# HDMI_RGB_LVDS_fertig_V6.net
KiCad netlist of a schematic drawn in EAGLE
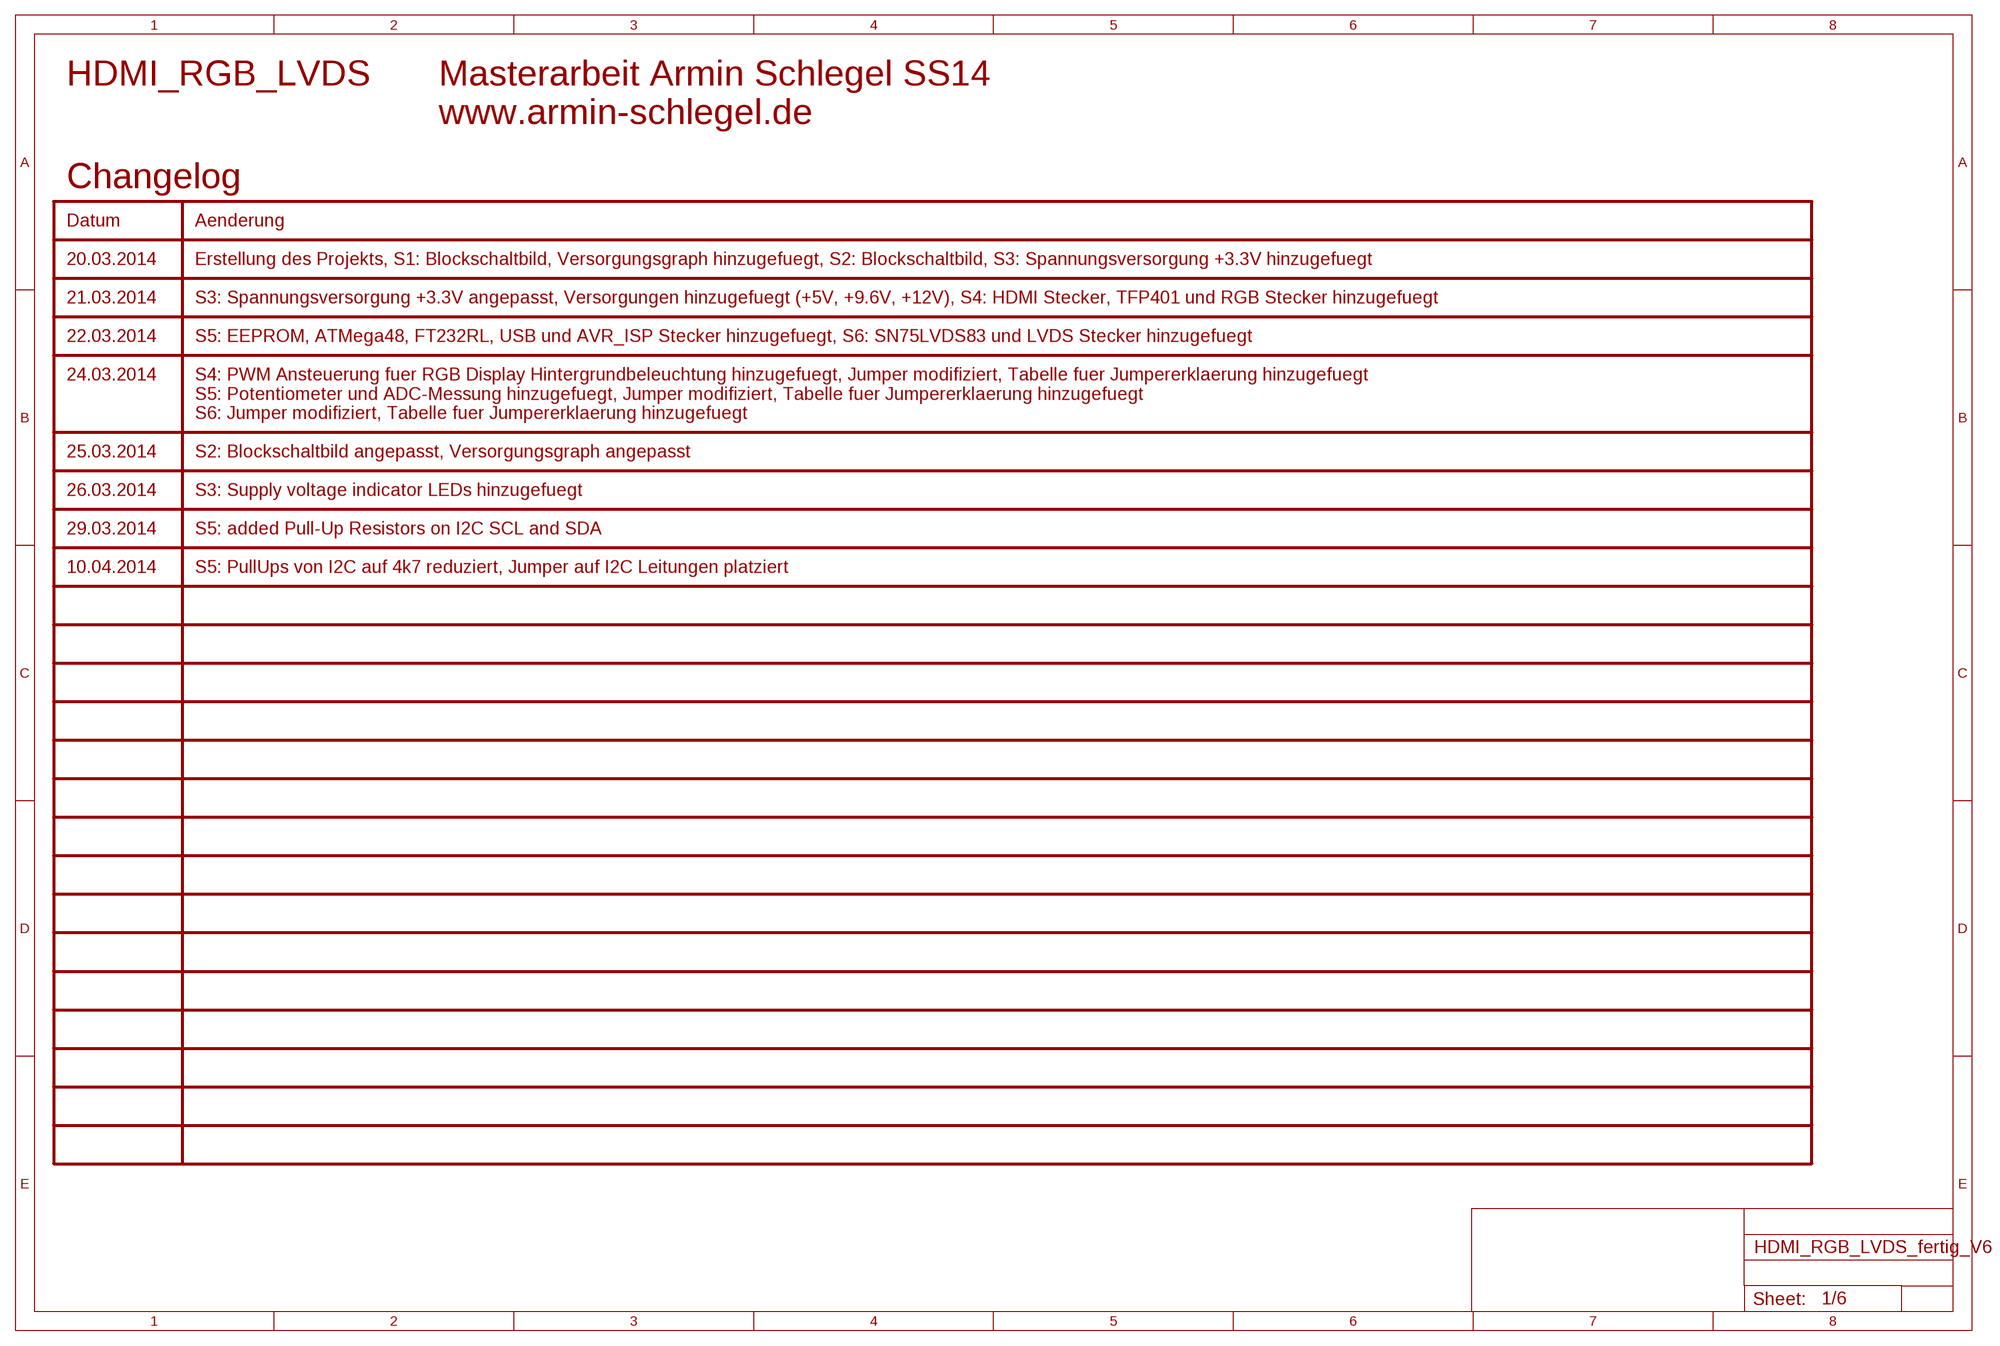
[diagram p0: schematic, sheet 1]
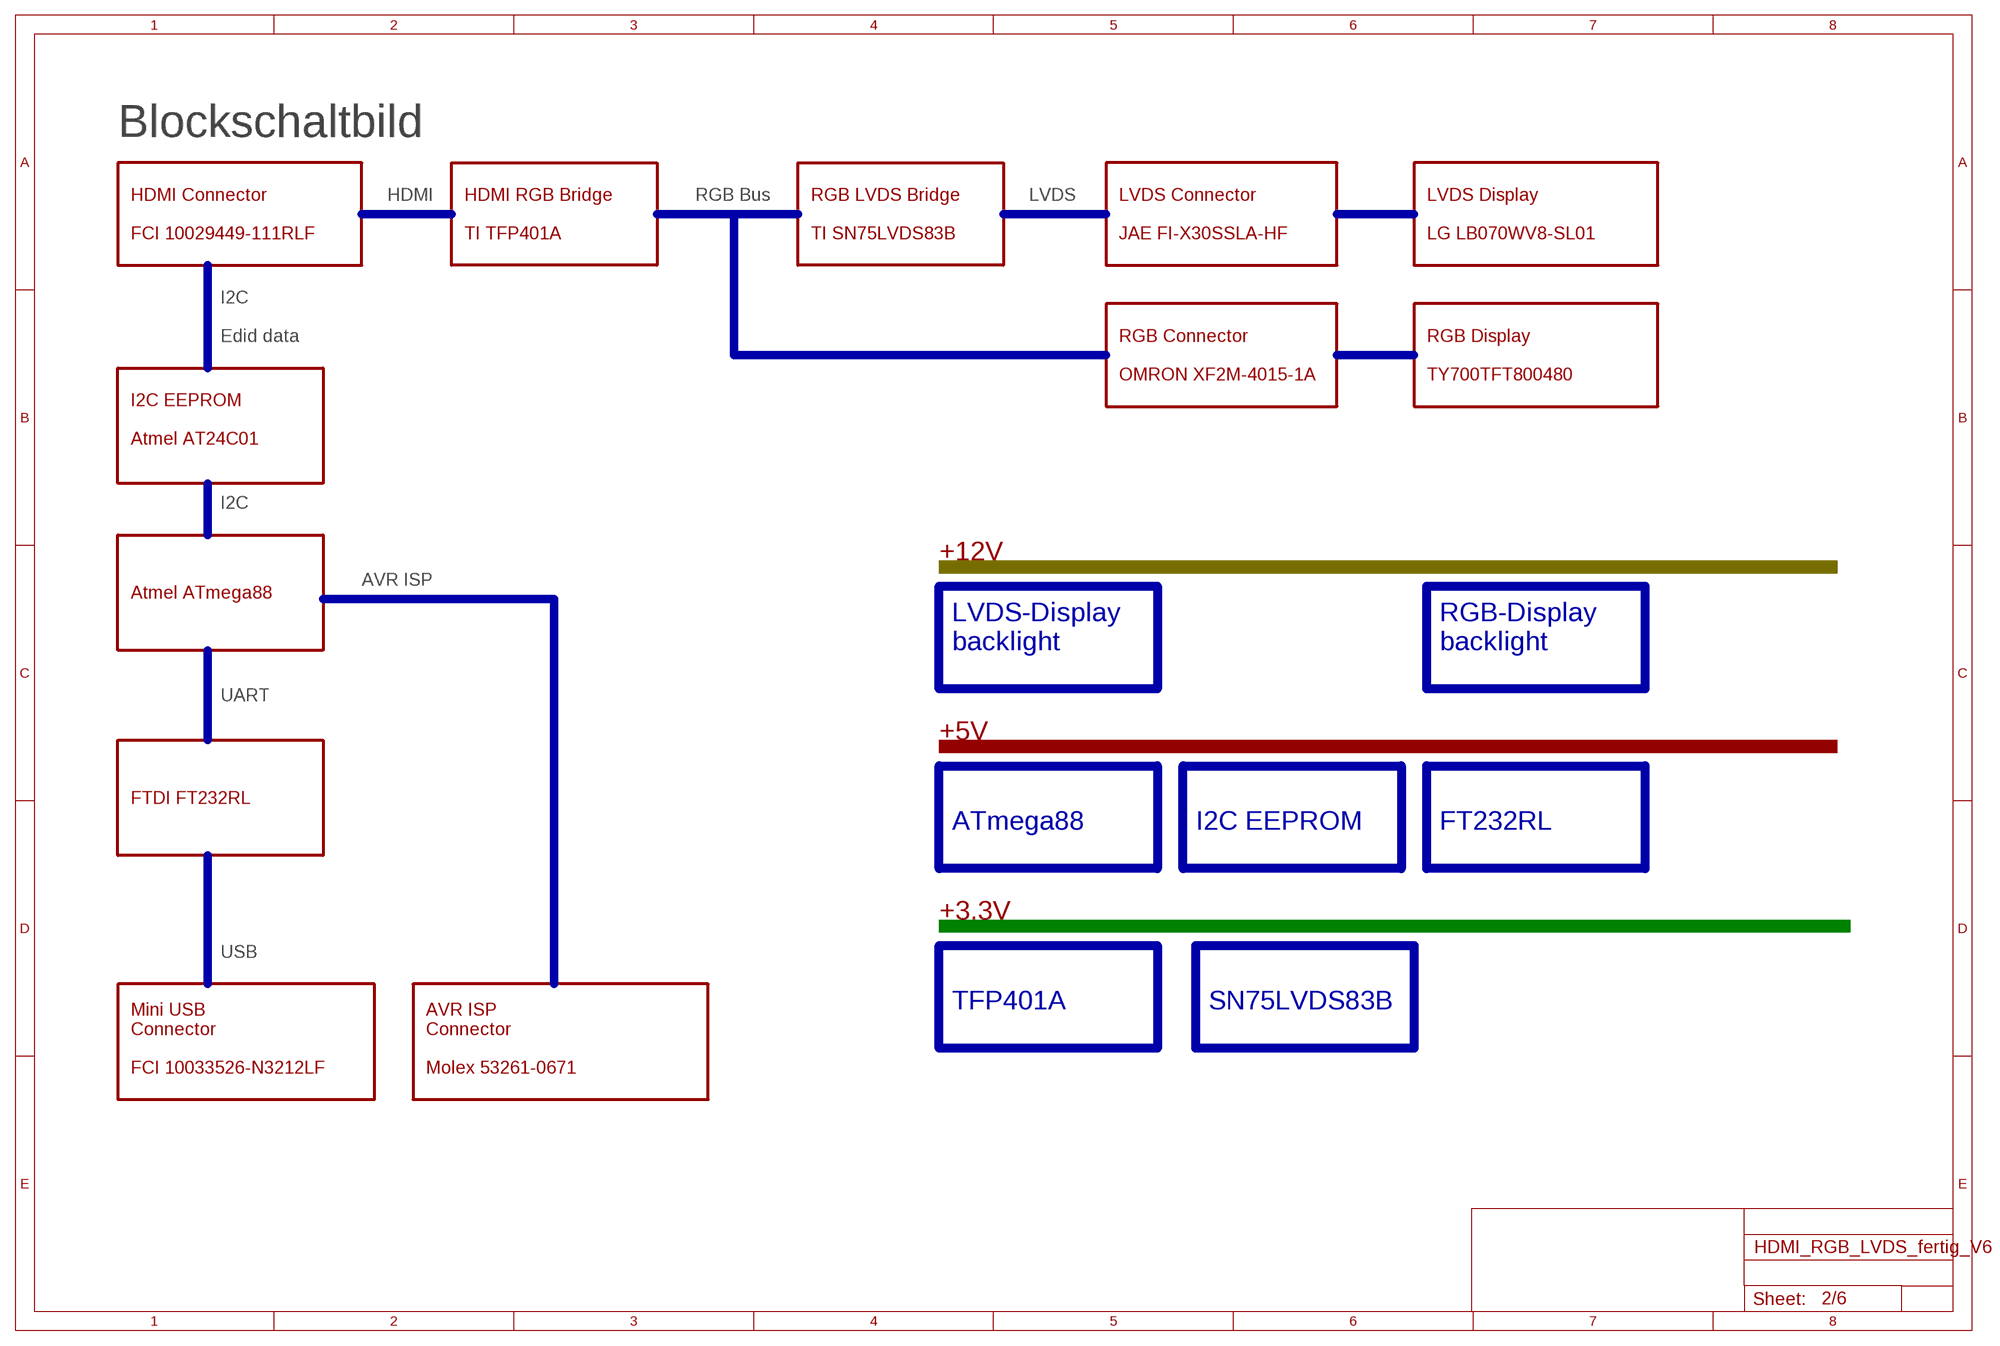
[diagram p1: schematic, sheet 2]
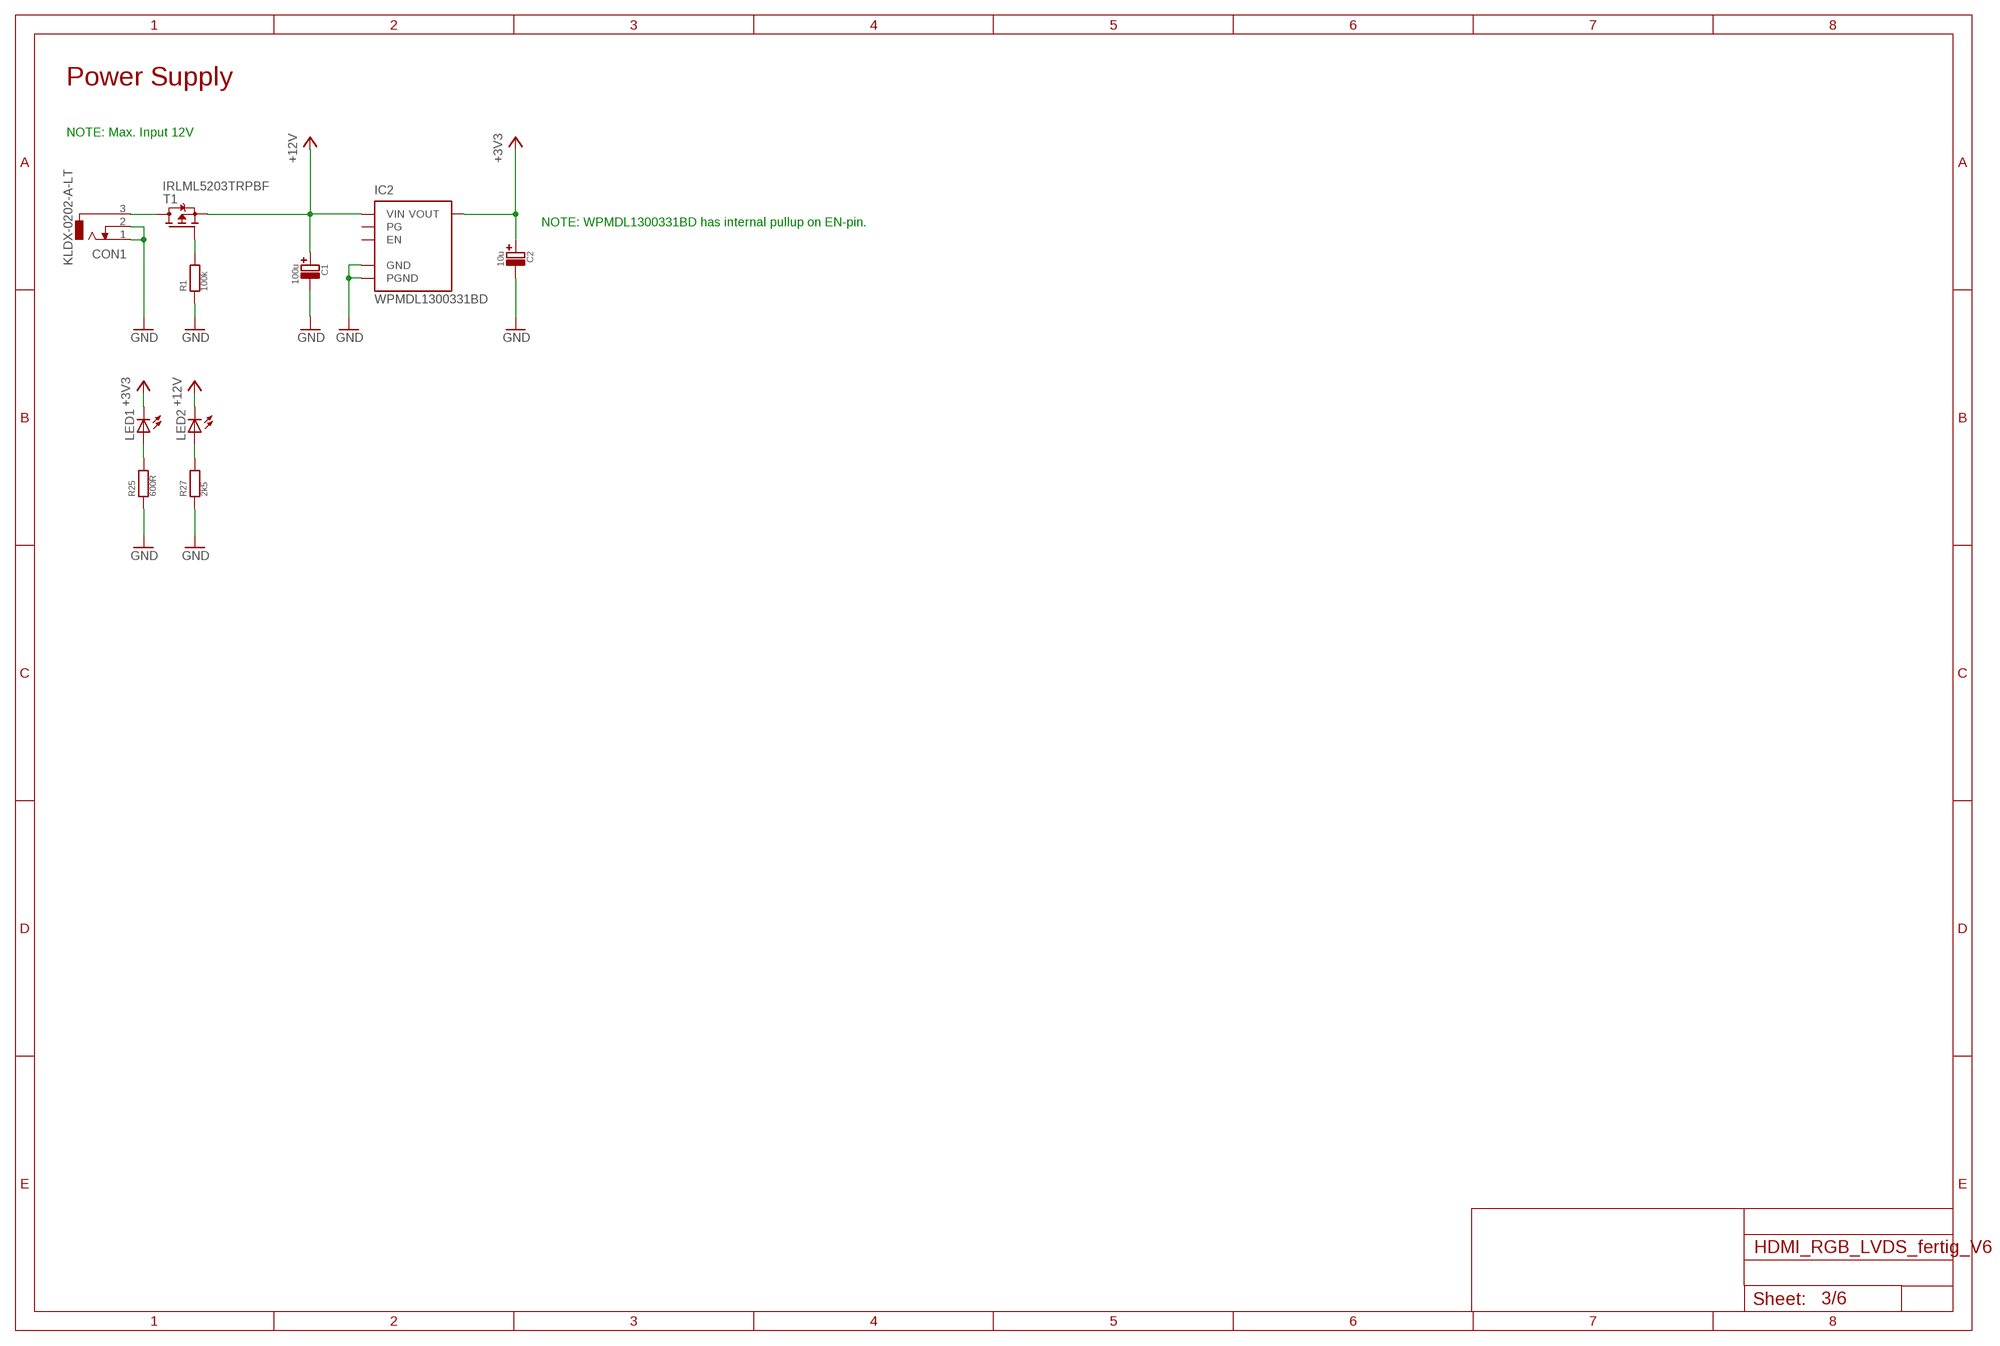
[diagram p2: schematic, sheet 3]
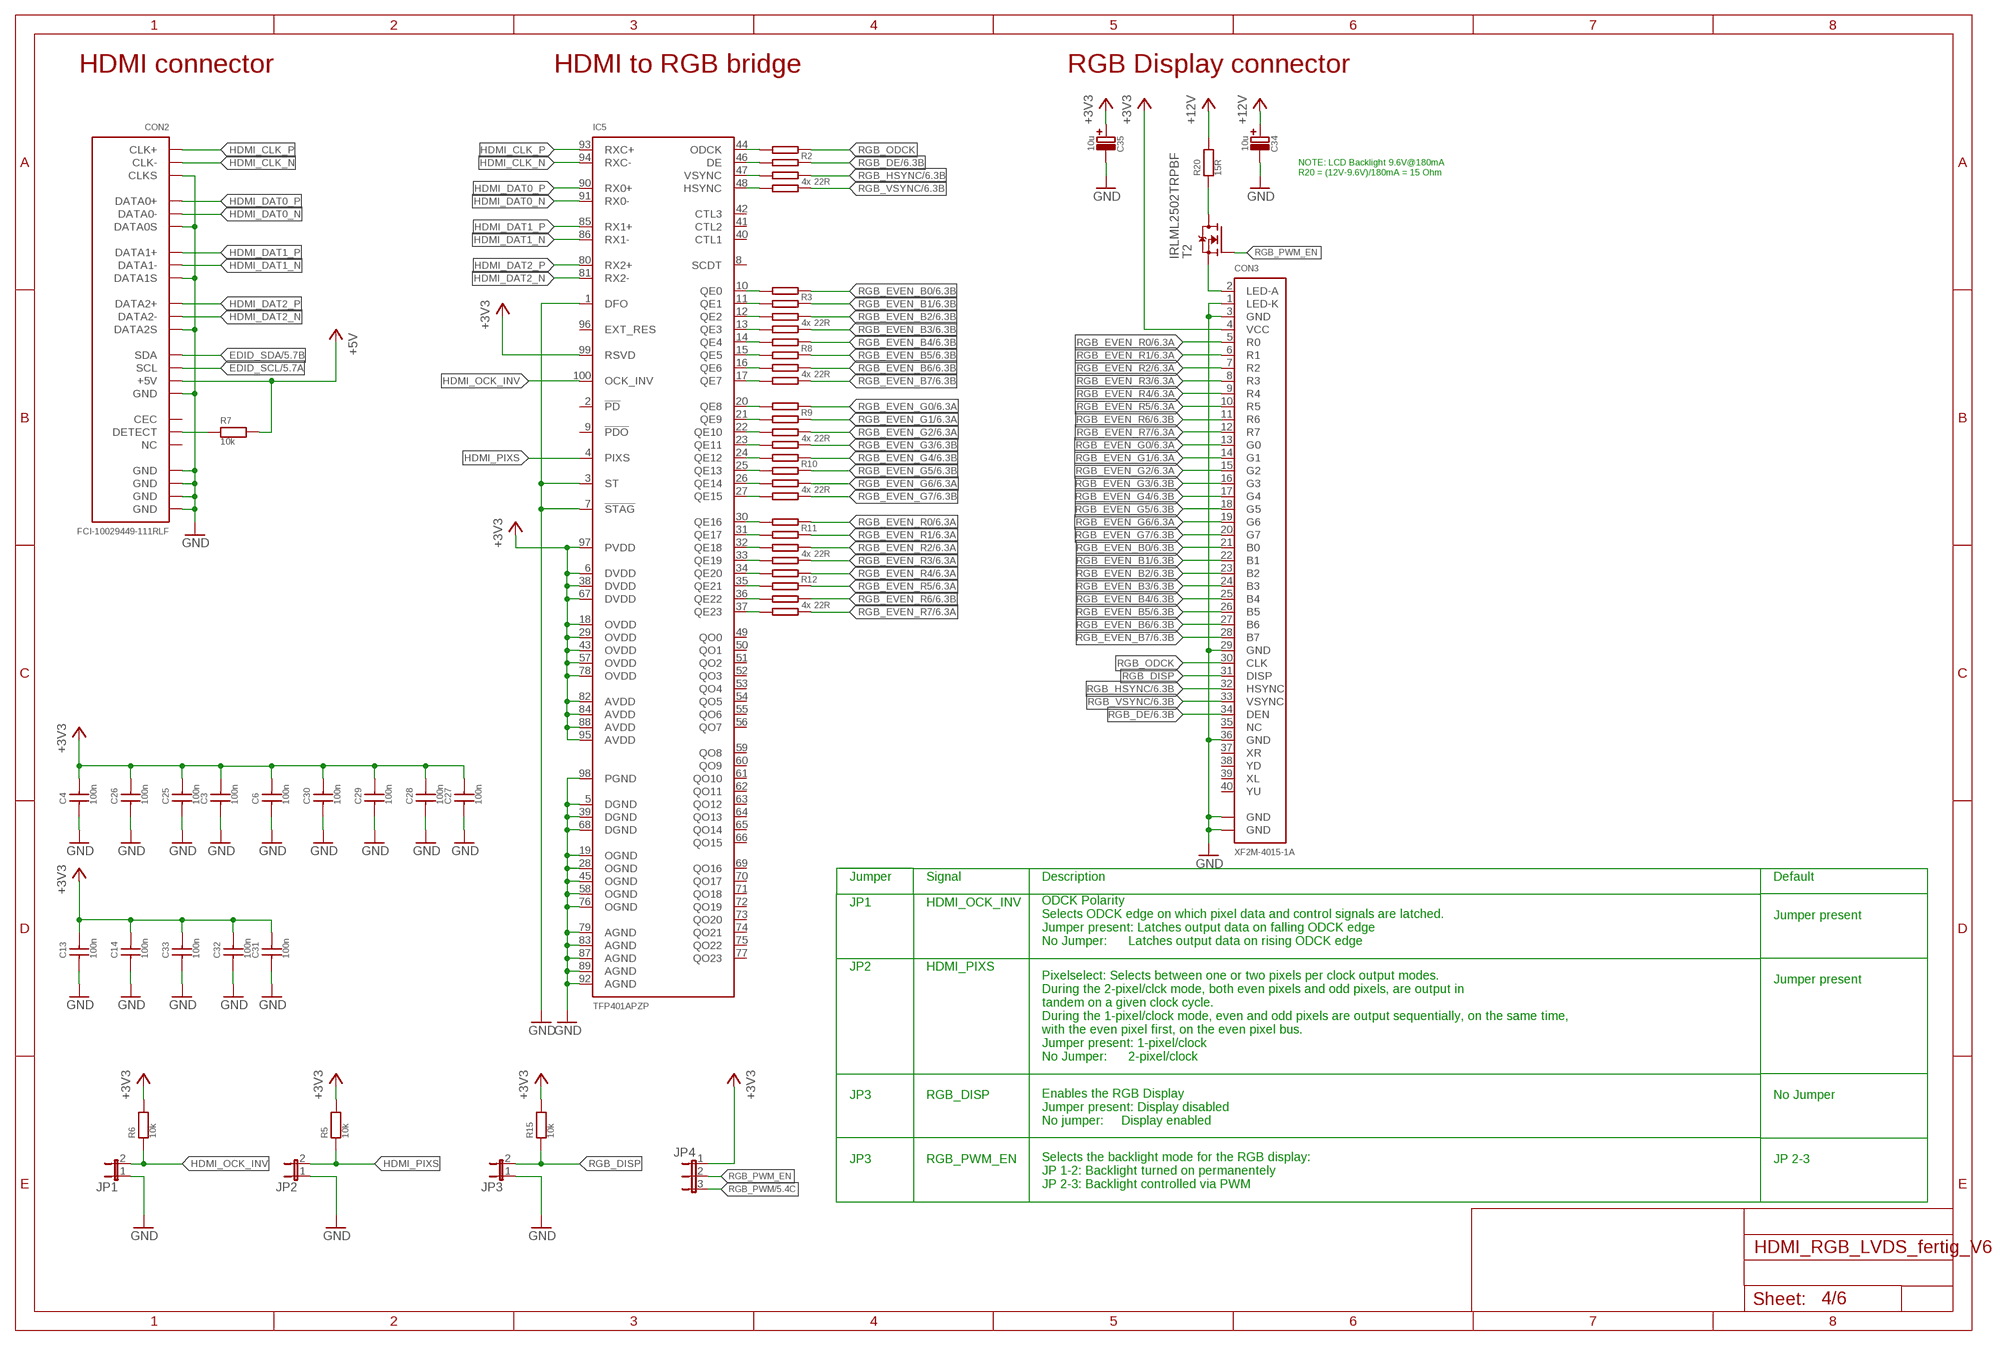
[diagram p3: schematic, sheet 4]
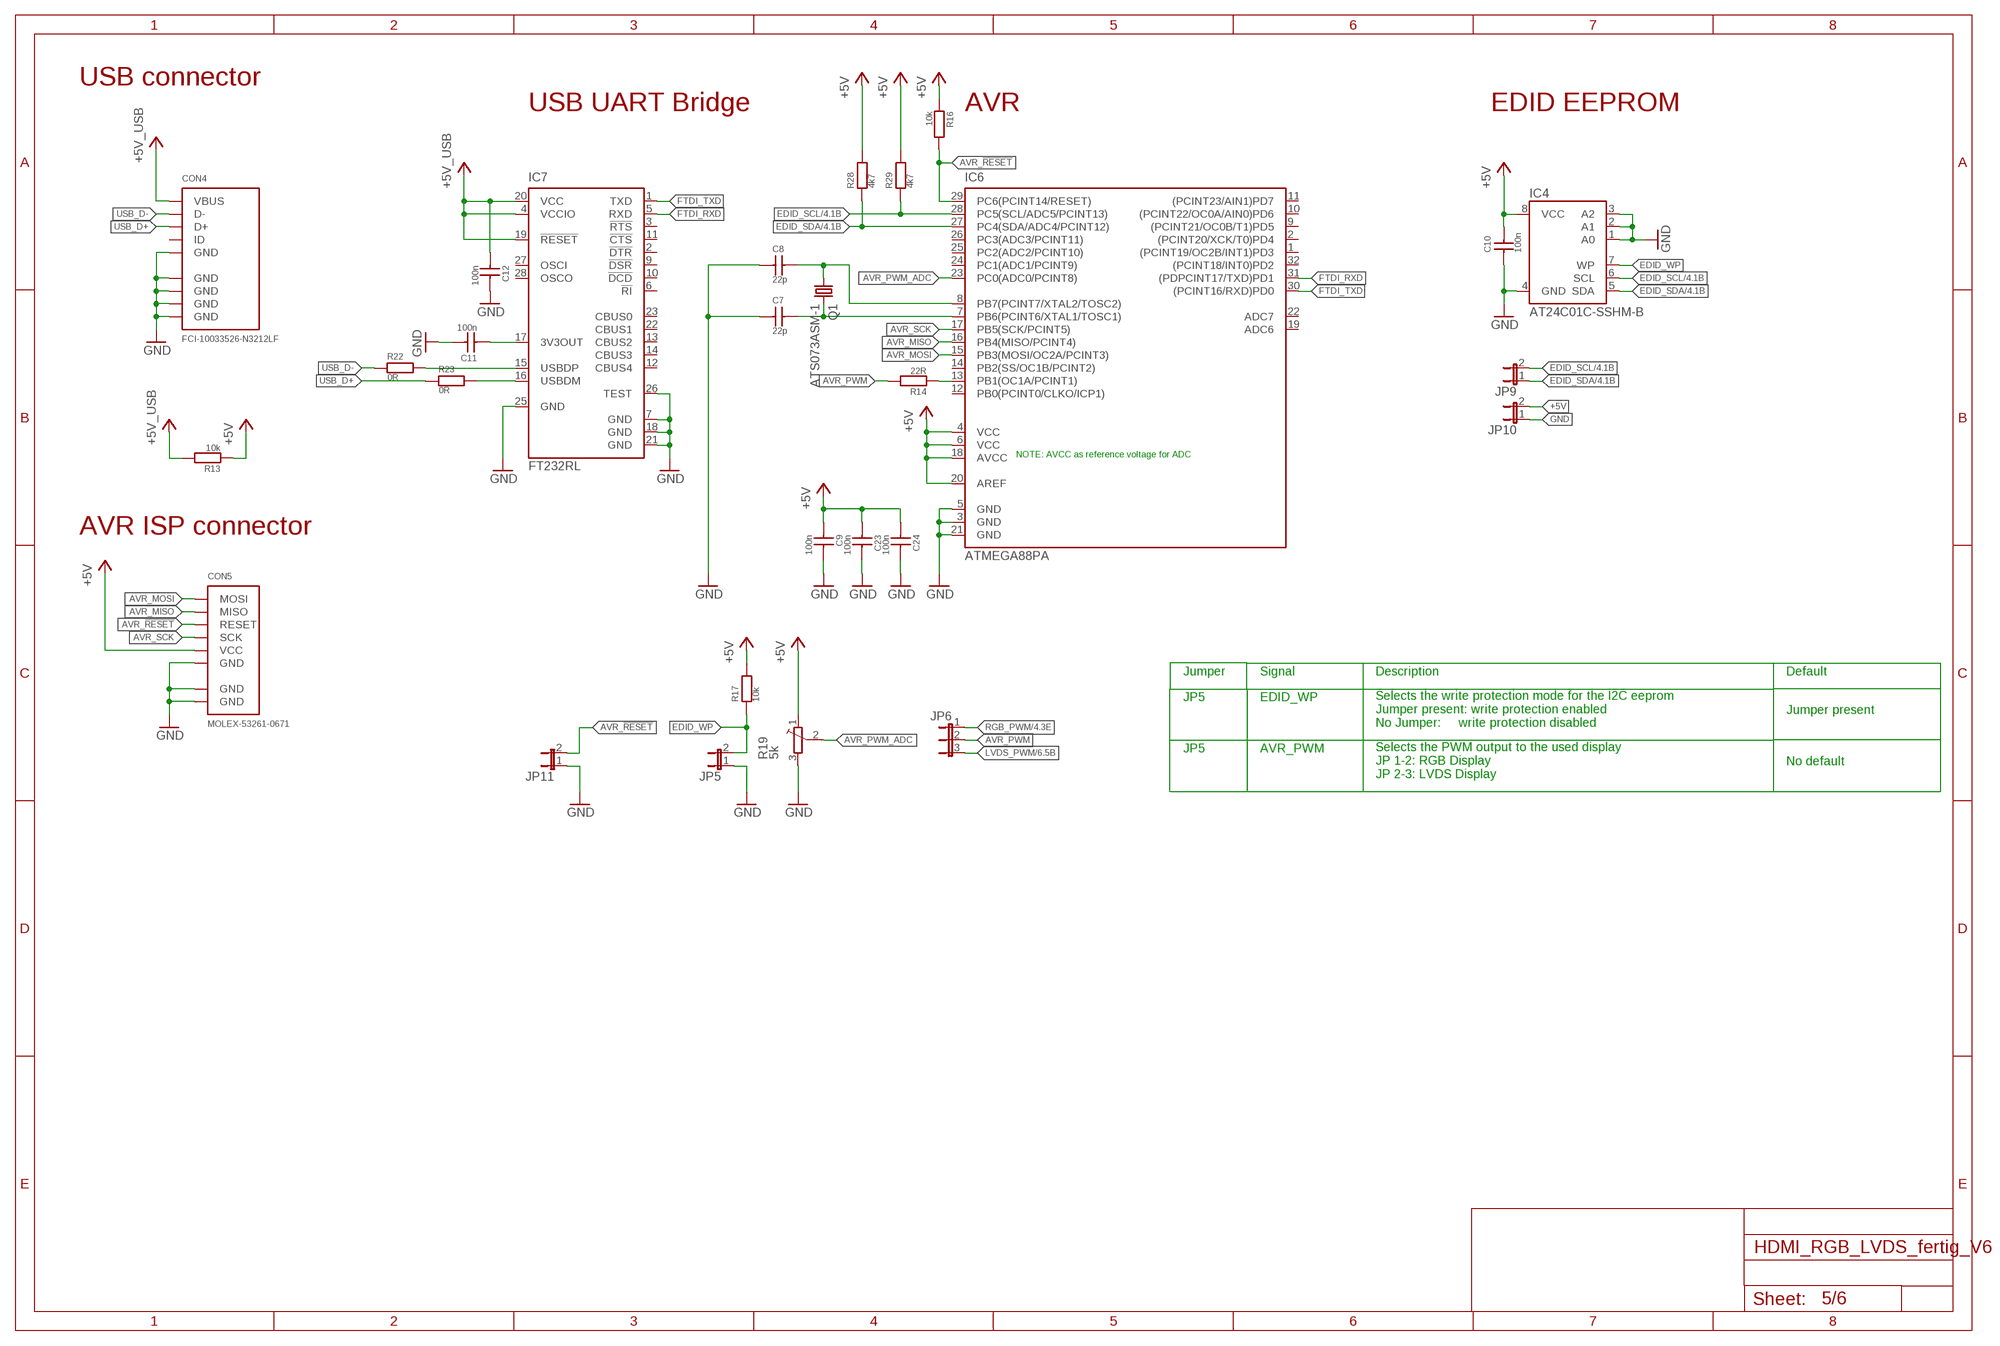
[diagram p4: schematic, sheet 5]
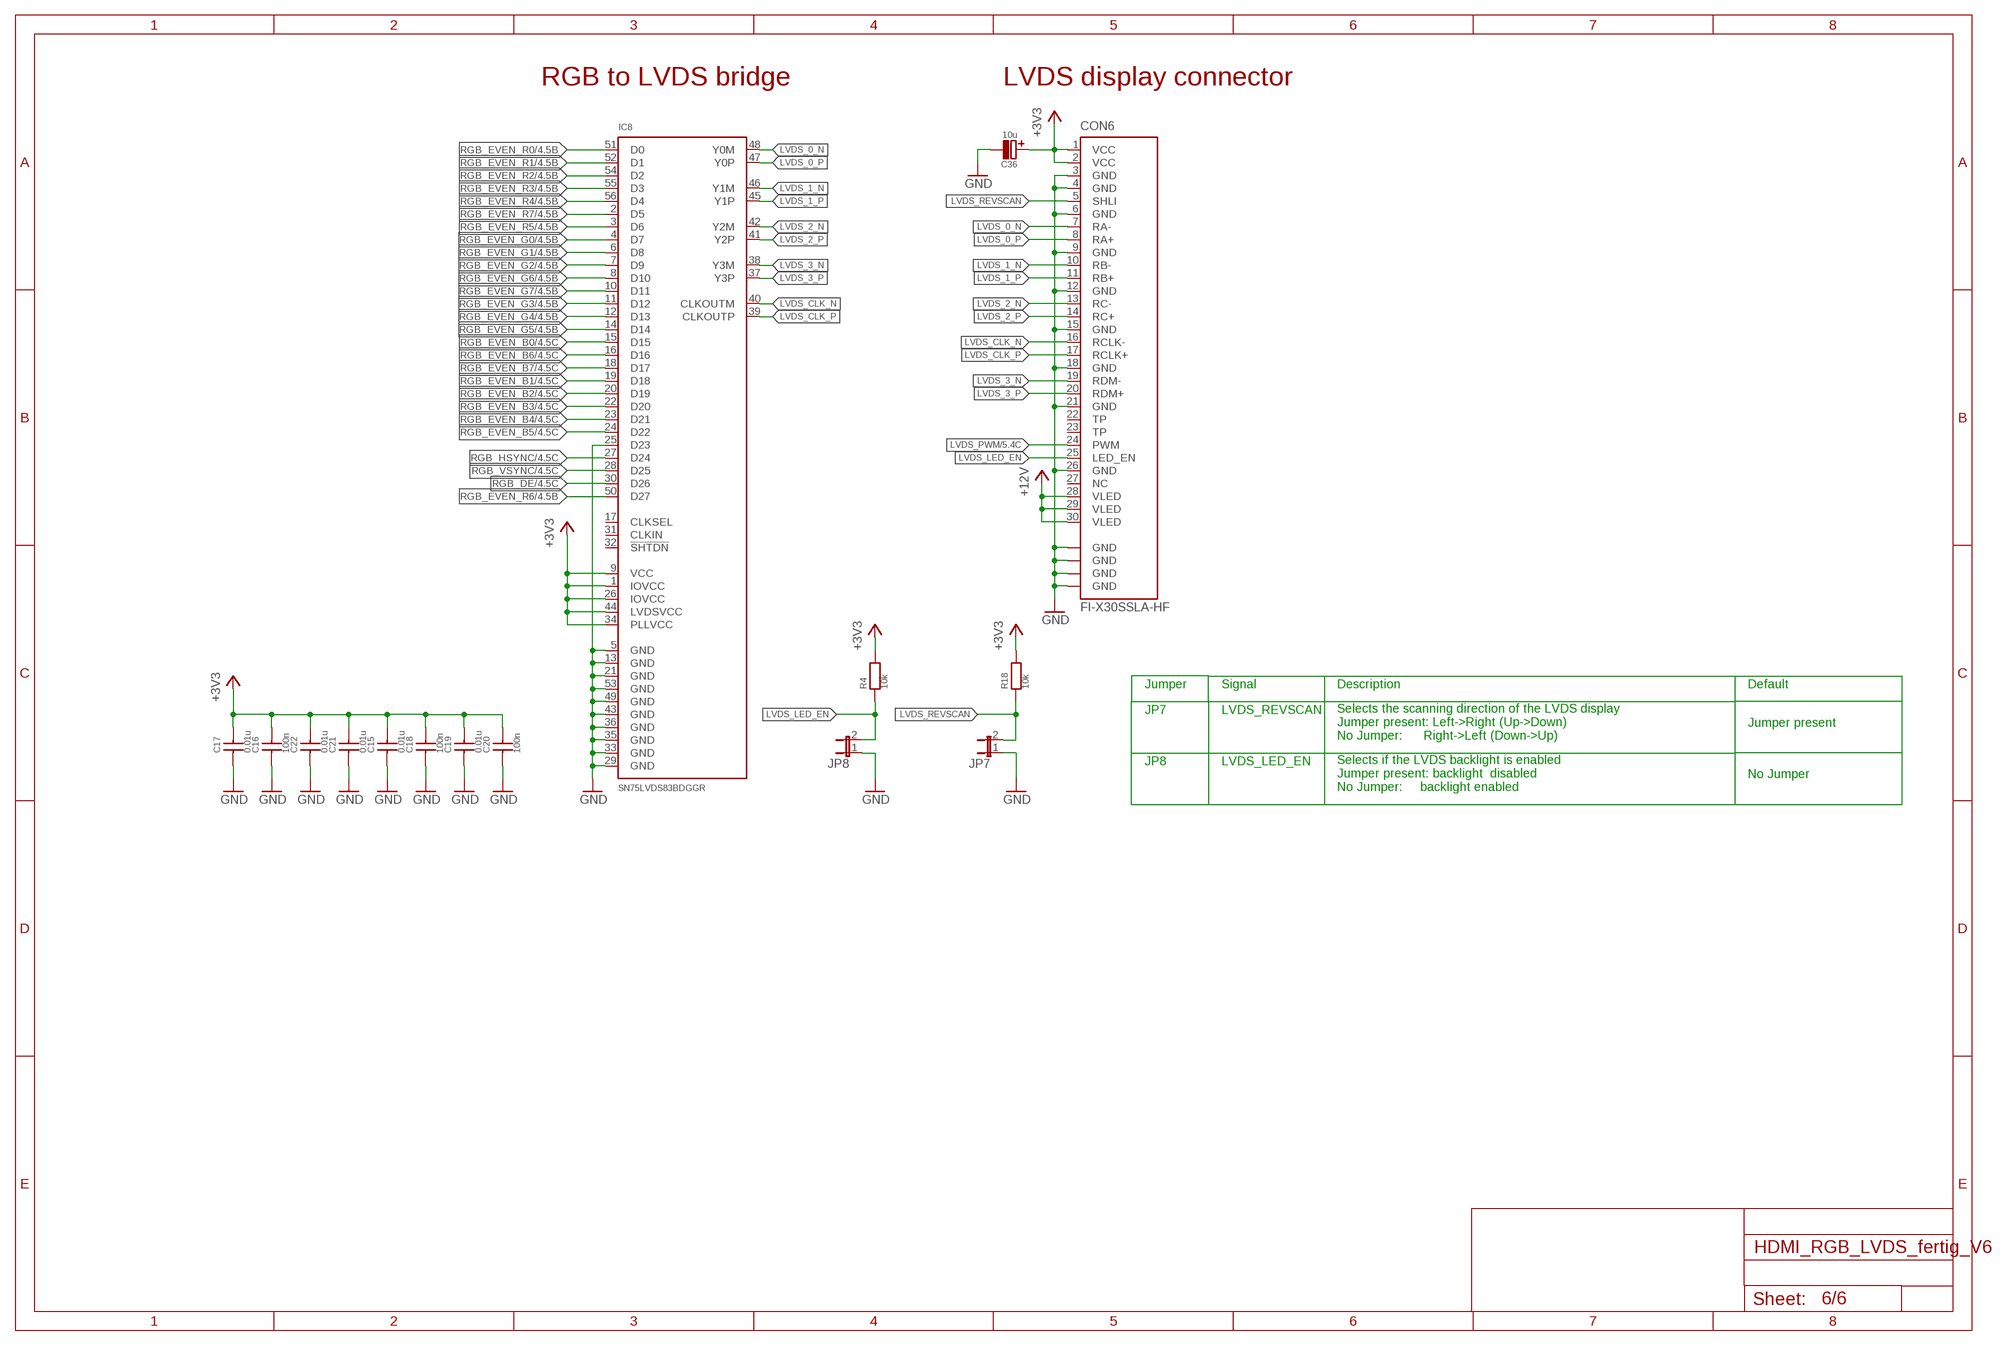
[diagram p5: schematic, sheet 6]

(export (version "E")
  (design (tool "Eeschema 10.0.6"))
  (components
    (comp (ref "C1")
      (value "100u")
      (footprint "eagle-import:C_POL_6X6MM")
      (libsource (lib "eagle-import") (part "RSS1C101MCN1GS"))
    )
    (comp (ref "C2")
      (value "10u")
      (footprint "eagle-import:C_POL_4X4MM")
      (libsource (lib "eagle-import") (part "C_POL4X4MM"))
    )
    (comp (ref "CON1")
      (value "KLDX-0202-A-LT")
      (footprint "eagle-import:KLDX-0202-A-LT")
      (libsource (lib "eagle-import") (part "KLDX-0202-A-LT"))
    )
    (comp (ref "IC2")
      (value "WPMDL1300331BD")
      (footprint "eagle-import:TO263-5")
      (libsource (lib "eagle-import") (part "WPMDL1300331BD"))
    )
    (comp (ref "LED1")
      (value "LED0402")
      (footprint "eagle-import:LED0402")
      (libsource (lib "eagle-import") (part "LED0402"))
    )
    (comp (ref "LED2")
      (value "LED0402")
      (footprint "eagle-import:LED0402")
      (libsource (lib "eagle-import") (part "LED0402"))
    )
    (comp (ref "R1")
      (value "100k")
      (footprint "eagle-import:R0402")
      (libsource (lib "eagle-import") (part "R0402"))
    )
    (comp (ref "R25")
      (value "600R")
      (footprint "eagle-import:R0402")
      (libsource (lib "eagle-import") (part "R0402"))
    )
    (comp (ref "R27")
      (value "2k5")
      (footprint "eagle-import:R0402")
      (libsource (lib "eagle-import") (part "R0402"))
    )
    (comp (ref "T1")
      (value "IRLML5203TRPBF")
      (footprint "eagle-import:SOT23")
      (libsource (lib "eagle-import") (part "IRLML5203TRPBF"))
    )
    (comp (ref "U$2")
      (value "FRAME_A3_LANDSCAPE")
      (footprint "eagle-import:FRAME")
      (libsource (lib "eagle-import") (part "FRAME_A3_LANDSCAPE"))
    )
    (comp (ref "C3")
      (value "100n")
      (footprint "eagle-import:C0402")
      (libsource (lib "eagle-import") (part "C_SMD0402"))
    )
    (comp (ref "C4")
      (value "100n")
      (footprint "eagle-import:C0402")
      (libsource (lib "eagle-import") (part "C_SMD0402"))
    )
    (comp (ref "C6")
      (value "100n")
      (footprint "eagle-import:C0402")
      (libsource (lib "eagle-import") (part "C_SMD0402"))
    )
    (comp (ref "C13")
      (value "100n")
      (footprint "eagle-import:C0402")
      (libsource (lib "eagle-import") (part "C_SMD0402"))
    )
    (comp (ref "C14")
      (value "100n")
      (footprint "eagle-import:C0402")
      (libsource (lib "eagle-import") (part "C_SMD0402"))
    )
    (comp (ref "C25")
      (value "100n")
      (footprint "eagle-import:C0402")
      (libsource (lib "eagle-import") (part "C_SMD0402"))
    )
    (comp (ref "C26")
      (value "100n")
      (footprint "eagle-import:C0402")
      (libsource (lib "eagle-import") (part "C_SMD0402"))
    )
    (comp (ref "C27")
      (value "100n")
      (footprint "eagle-import:C0402")
      (libsource (lib "eagle-import") (part "C_SMD0402"))
    )
    (comp (ref "C28")
      (value "100n")
      (footprint "eagle-import:C0402")
      (libsource (lib "eagle-import") (part "C_SMD0402"))
    )
    (comp (ref "C29")
      (value "100n")
      (footprint "eagle-import:C0402")
      (libsource (lib "eagle-import") (part "C_SMD0402"))
    )
    (comp (ref "C30")
      (value "100n")
      (footprint "eagle-import:C0402")
      (libsource (lib "eagle-import") (part "C_SMD0402"))
    )
    (comp (ref "C31")
      (value "100n")
      (footprint "eagle-import:C0402")
      (libsource (lib "eagle-import") (part "C_SMD0402"))
    )
    (comp (ref "C32")
      (value "100n")
      (footprint "eagle-import:C0402")
      (libsource (lib "eagle-import") (part "C_SMD0402"))
    )
    (comp (ref "C33")
      (value "100n")
      (footprint "eagle-import:C0402")
      (libsource (lib "eagle-import") (part "C_SMD0402"))
    )
    (comp (ref "C34")
      (value "10u")
      (footprint "eagle-import:C_POL_4X4MM")
      (libsource (lib "eagle-import") (part "C_POL4X4MM"))
    )
    (comp (ref "C35")
      (value "10u")
      (footprint "eagle-import:C_POL_4X4MM")
      (libsource (lib "eagle-import") (part "C_POL4X4MM"))
    )
    (comp (ref "CON2")
      (value "FCI-10029449-111RLF")
      (footprint "eagle-import:FCI-10029449-111RLF")
      (libsource (lib "eagle-import") (part "FCI-10029449-111RLF"))
    )
    (comp (ref "CON3")
      (value "XF2M-4015-1A")
      (footprint "eagle-import:XF2M-4015-1A")
      (libsource (lib "eagle-import") (part "XF2M-4015-1A"))
    )
    (comp (ref "IC5")
      (value "TFP401APZP")
      (footprint "eagle-import:HTQFP-100")
      (libsource (lib "eagle-import") (part "TFP401APZP"))
    )
    (comp (ref "JP1")
      (value "JUMPER2")
      (footprint "eagle-import:JUMPER2_THROUGHHOLE")
      (libsource (lib "eagle-import") (part "JUMPER2"))
    )
    (comp (ref "JP2")
      (value "JUMPER2")
      (footprint "eagle-import:JUMPER2_THROUGHHOLE")
      (libsource (lib "eagle-import") (part "JUMPER2"))
    )
    (comp (ref "JP3")
      (value "JUMPER2")
      (footprint "eagle-import:JUMPER2_THROUGHHOLE")
      (libsource (lib "eagle-import") (part "JUMPER2"))
    )
    (comp (ref "JP4")
      (value "JUMPER3")
      (footprint "eagle-import:JUMPER3_THROUGHHOLE")
      (libsource (lib "eagle-import") (part "JUMPER3"))
    )
    (comp (ref "R2")
      (value "22R")
      (footprint "eagle-import:R-ARRAY-4X0603")
      (libsource (lib "eagle-import") (part "CTR-742C083220JP-4X22R-4X0603"))
    )
    (comp (ref "R3")
      (value "22R")
      (footprint "eagle-import:R-ARRAY-4X0603")
      (libsource (lib "eagle-import") (part "CTR-742C083220JP-4X22R-4X0603"))
    )
    (comp (ref "R5")
      (value "10k")
      (footprint "eagle-import:R0402")
      (libsource (lib "eagle-import") (part "R0402"))
    )
    (comp (ref "R6")
      (value "10k")
      (footprint "eagle-import:R0402")
      (libsource (lib "eagle-import") (part "R0402"))
    )
    (comp (ref "R7")
      (value "10k")
      (footprint "eagle-import:R0402")
      (libsource (lib "eagle-import") (part "R0402"))
    )
    (comp (ref "R8")
      (value "22R")
      (footprint "eagle-import:R-ARRAY-4X0603")
      (libsource (lib "eagle-import") (part "CTR-742C083220JP-4X22R-4X0603"))
    )
    (comp (ref "R9")
      (value "22R")
      (footprint "eagle-import:R-ARRAY-4X0603")
      (libsource (lib "eagle-import") (part "CTR-742C083220JP-4X22R-4X0603"))
    )
    (comp (ref "R10")
      (value "22R")
      (footprint "eagle-import:R-ARRAY-4X0603")
      (libsource (lib "eagle-import") (part "CTR-742C083220JP-4X22R-4X0603"))
    )
    (comp (ref "R11")
      (value "22R")
      (footprint "eagle-import:R-ARRAY-4X0603")
      (libsource (lib "eagle-import") (part "CTR-742C083220JP-4X22R-4X0603"))
    )
    (comp (ref "R12")
      (value "22R")
      (footprint "eagle-import:R-ARRAY-4X0603")
      (libsource (lib "eagle-import") (part "CTR-742C083220JP-4X22R-4X0603"))
    )
    (comp (ref "R15")
      (value "10k")
      (footprint "eagle-import:R0402")
      (libsource (lib "eagle-import") (part "R0402"))
    )
    (comp (ref "R20")
      (value "15R")
      (footprint "eagle-import:R2512")
      (libsource (lib "eagle-import") (part "R2512"))
    )
    (comp (ref "T2")
      (value "IRLML2502TRPBF")
      (footprint "eagle-import:SOT23")
      (libsource (lib "eagle-import") (part "IRLML2502TRPBF"))
    )
    (comp (ref "U$3")
      (value "FRAME_A3_LANDSCAPE")
      (footprint "eagle-import:FRAME")
      (libsource (lib "eagle-import") (part "FRAME_A3_LANDSCAPE"))
    )
    (comp (ref "C7")
      (value "22p")
      (footprint "eagle-import:C0402")
      (libsource (lib "eagle-import") (part "C_SMD0402"))
    )
    (comp (ref "C8")
      (value "22p")
      (footprint "eagle-import:C0402")
      (libsource (lib "eagle-import") (part "C_SMD0402"))
    )
    (comp (ref "C9")
      (value "100n")
      (footprint "eagle-import:C0402")
      (libsource (lib "eagle-import") (part "C_SMD0402"))
    )
    (comp (ref "C10")
      (value "100n")
      (footprint "eagle-import:C0402")
      (libsource (lib "eagle-import") (part "C_SMD0402"))
    )
    (comp (ref "C11")
      (value "100n")
      (footprint "eagle-import:C0402")
      (libsource (lib "eagle-import") (part "C_SMD0402"))
    )
    (comp (ref "C12")
      (value "100n")
      (footprint "eagle-import:C0402")
      (libsource (lib "eagle-import") (part "C_SMD0402"))
    )
    (comp (ref "C23")
      (value "100n")
      (footprint "eagle-import:C0402")
      (libsource (lib "eagle-import") (part "C_SMD0402"))
    )
    (comp (ref "C24")
      (value "100n")
      (footprint "eagle-import:C0402")
      (libsource (lib "eagle-import") (part "C_SMD0402"))
    )
    (comp (ref "CON4")
      (value "FCI-10033526-N3212LF")
      (footprint "eagle-import:FCI-10033526-N3212LF")
      (libsource (lib "eagle-import") (part "FCI-10033526-N3212LF"))
    )
    (comp (ref "CON5")
      (value "MOLEX-53261-0671")
      (footprint "eagle-import:MOLEX-53261-0671")
      (libsource (lib "eagle-import") (part "MOLEX-53261-0671"))
    )
    (comp (ref "IC4")
      (value "AT24C01C-SSHM-B")
      (footprint "eagle-import:SOIC8")
      (libsource (lib "eagle-import") (part "AT24C01C-SSHM-B"))
    )
    (comp (ref "IC6")
      (value "ATMEGA88PA")
      (footprint "eagle-import:TQFP32")
      (libsource (lib "eagle-import") (part "ATMEGA48A-AU"))
    )
    (comp (ref "IC7")
      (value "FT232RL")
      (footprint "eagle-import:SSOP28")
      (libsource (lib "eagle-import") (part "FT232RL"))
    )
    (comp (ref "JP5")
      (value "JUMPER2")
      (footprint "eagle-import:JUMPER2_THROUGHHOLE")
      (libsource (lib "eagle-import") (part "JUMPER2"))
    )
    (comp (ref "JP6")
      (value "JUMPER3")
      (footprint "eagle-import:JUMPER3_THROUGHHOLE")
      (libsource (lib "eagle-import") (part "JUMPER3"))
    )
    (comp (ref "JP9")
      (value "JUMPER2")
      (footprint "eagle-import:JUMPER2_THROUGHHOLE")
      (libsource (lib "eagle-import") (part "JUMPER2"))
    )
    (comp (ref "JP10")
      (value "JUMPER2")
      (footprint "eagle-import:JUMPER2_THROUGHHOLE")
      (libsource (lib "eagle-import") (part "JUMPER2"))
    )
    (comp (ref "JP11")
      (value "JUMPER2")
      (footprint "eagle-import:JUMPER2_THROUGHHOLE")
      (libsource (lib "eagle-import") (part "JUMPER2"))
    )
    (comp (ref "Q1")
      (value "ATS073ASM-1")
      (footprint "eagle-import:HC49_USSM")
      (libsource (lib "eagle-import") (part "ATS073ASM-1"))
    )
    (comp (ref "R13")
      (value "10k")
      (footprint "eagle-import:R0402")
      (libsource (lib "eagle-import") (part "R0402"))
    )
    (comp (ref "R14")
      (value "22R")
      (footprint "eagle-import:R0402")
      (libsource (lib "eagle-import") (part "R0402"))
    )
    (comp (ref "R16")
      (value "10k")
      (footprint "eagle-import:R0402")
      (libsource (lib "eagle-import") (part "R0402"))
    )
    (comp (ref "R17")
      (value "10k")
      (footprint "eagle-import:R0402")
      (libsource (lib "eagle-import") (part "R0402"))
    )
    (comp (ref "R19")
      (value "5k")
      (footprint "eagle-import:35WR5KLFTR")
      (libsource (lib "eagle-import") (part "35WR5KLFTR"))
    )
    (comp (ref "R22")
      (value "0R")
      (footprint "eagle-import:R0402")
      (libsource (lib "eagle-import") (part "R0402"))
    )
    (comp (ref "R23")
      (value "0R")
      (footprint "eagle-import:R0402")
      (libsource (lib "eagle-import") (part "R0402"))
    )
    (comp (ref "R28")
      (value "4k7")
      (footprint "eagle-import:R0402")
      (libsource (lib "eagle-import") (part "R0402"))
    )
    (comp (ref "R29")
      (value "4k7")
      (footprint "eagle-import:R0402")
      (libsource (lib "eagle-import") (part "R0402"))
    )
    (comp (ref "U$4")
      (value "FRAME_A3_LANDSCAPE")
      (footprint "eagle-import:FRAME")
      (libsource (lib "eagle-import") (part "FRAME_A3_LANDSCAPE"))
    )
    (comp (ref "C15")
      (value "0.01u")
      (footprint "eagle-import:C0402")
      (libsource (lib "eagle-import") (part "C_SMD0402"))
    )
    (comp (ref "C16")
      (value "100n")
      (footprint "eagle-import:C0402")
      (libsource (lib "eagle-import") (part "C_SMD0402"))
    )
    (comp (ref "C17")
      (value "0.01u")
      (footprint "eagle-import:C0402")
      (libsource (lib "eagle-import") (part "C_SMD0402"))
    )
    (comp (ref "C18")
      (value "100n")
      (footprint "eagle-import:C0402")
      (libsource (lib "eagle-import") (part "C_SMD0402"))
    )
    (comp (ref "C19")
      (value "0.01u")
      (footprint "eagle-import:C0402")
      (libsource (lib "eagle-import") (part "C_SMD0402"))
    )
    (comp (ref "C20")
      (value "100n")
      (footprint "eagle-import:C0402")
      (libsource (lib "eagle-import") (part "C_SMD0402"))
    )
    (comp (ref "C21")
      (value "0.01u")
      (footprint "eagle-import:C0402")
      (libsource (lib "eagle-import") (part "C_SMD0402"))
    )
    (comp (ref "C22")
      (value "0.01u")
      (footprint "eagle-import:C0402")
      (libsource (lib "eagle-import") (part "C_SMD0402"))
    )
    (comp (ref "C36")
      (value "10u")
      (footprint "eagle-import:C_POL_4X4MM")
      (libsource (lib "eagle-import") (part "C_POL4X4MM"))
    )
    (comp (ref "CON6")
      (value "FI-X30SSLA-HF")
      (footprint "eagle-import:FI-X30SSLA-HF")
      (libsource (lib "eagle-import") (part "FI-X30SSLA-HF"))
    )
    (comp (ref "IC8")
      (value "SN75LVDS83BDGGR")
      (footprint "eagle-import:TSSOP-56")
      (libsource (lib "eagle-import") (part "SN75LVDS83BDGGR"))
    )
    (comp (ref "JP7")
      (value "JUMPER2")
      (footprint "eagle-import:JUMPER2_THROUGHHOLE")
      (libsource (lib "eagle-import") (part "JUMPER2"))
    )
    (comp (ref "JP8")
      (value "JUMPER2")
      (footprint "eagle-import:JUMPER2_THROUGHHOLE")
      (libsource (lib "eagle-import") (part "JUMPER2"))
    )
    (comp (ref "R4")
      (value "10k")
      (footprint "eagle-import:R0402")
      (libsource (lib "eagle-import") (part "R0402"))
    )
    (comp (ref "R18")
      (value "10k")
      (footprint "eagle-import:R0402")
      (libsource (lib "eagle-import") (part "R0402"))
    )
    (comp (ref "U$5")
      (value "FRAME_A3_LANDSCAPE")
      (footprint "eagle-import:FRAME")
      (libsource (lib "eagle-import") (part "FRAME_A3_LANDSCAPE"))
    )
    (comp (ref "U$15")
      (value "FRAME_A3_LANDSCAPE")
      (footprint "eagle-import:FRAME")
      (libsource (lib "eagle-import") (part "FRAME_A3_LANDSCAPE"))
    )
    (comp (ref "U$1")
      (value "FRAME_A3_LANDSCAPE")
      (footprint "eagle-import:FRAME")
      (libsource (lib "eagle-import") (part "FRAME_A3_LANDSCAPE"))
    )
  )
  (nets
    (net (code "3") (name "+3V3") (class "Default")
      (node (ref "C13") (pin "2") (pinfunction "P$2_2") (pintype "passive"))
      (node (ref "C14") (pin "2") (pinfunction "P$2_2") (pintype "passive"))
      (node (ref "C15") (pin "2") (pinfunction "P$2_2") (pintype "passive"))
      (node (ref "C16") (pin "2") (pinfunction "P$2_2") (pintype "passive"))
      (node (ref "C17") (pin "2") (pinfunction "P$2_2") (pintype "passive"))
      (node (ref "C18") (pin "2") (pinfunction "P$2_2") (pintype "passive"))
      (node (ref "C19") (pin "2") (pinfunction "P$2_2") (pintype "passive"))
      (node (ref "C2") (pin "+") (pinfunction "+_+") (pintype "passive"))
      (node (ref "C20") (pin "2") (pinfunction "P$2_2") (pintype "passive"))
      (node (ref "C21") (pin "2") (pinfunction "P$2_2") (pintype "passive"))
      (node (ref "C22") (pin "2") (pinfunction "P$2_2") (pintype "passive"))
      (node (ref "C25") (pin "2") (pinfunction "P$2_2") (pintype "passive"))
      (node (ref "C26") (pin "2") (pinfunction "P$2_2") (pintype "passive"))
      (node (ref "C27") (pin "2") (pinfunction "P$2_2") (pintype "passive"))
      (node (ref "C28") (pin "2") (pinfunction "P$2_2") (pintype "passive"))
      (node (ref "C29") (pin "2") (pinfunction "P$2_2") (pintype "passive"))
      (node (ref "C3") (pin "2") (pinfunction "P$2_2") (pintype "passive"))
      (node (ref "C30") (pin "2") (pinfunction "P$2_2") (pintype "passive"))
      (node (ref "C31") (pin "2") (pinfunction "P$2_2") (pintype "passive"))
      (node (ref "C32") (pin "2") (pinfunction "P$2_2") (pintype "passive"))
      (node (ref "C33") (pin "2") (pinfunction "P$2_2") (pintype "passive"))
      (node (ref "C35") (pin "+") (pinfunction "+_+") (pintype "passive"))
      (node (ref "C36") (pin "+") (pinfunction "+_+") (pintype "passive"))
      (node (ref "C4") (pin "2") (pinfunction "P$2_2") (pintype "passive"))
      (node (ref "C6") (pin "2") (pinfunction "P$2_2") (pintype "passive"))
      (node (ref "CON3") (pin "4") (pinfunction "VCC_4") (pintype "bidirectional"))
      (node (ref "CON6") (pin "1") (pinfunction "VCC_1") (pintype "bidirectional"))
      (node (ref "CON6") (pin "2") (pinfunction "VCC_2") (pintype "bidirectional"))
      (node (ref "IC2") (pin "3") (pinfunction "VOUT_3") (pintype "bidirectional"))
      (node (ref "IC5") (pin "18") (pinfunction "OVDD_18") (pintype "power_in"))
      (node (ref "IC5") (pin "29") (pinfunction "OVDD_29") (pintype "power_in"))
      (node (ref "IC5") (pin "38") (pinfunction "DVDD_38") (pintype "power_in"))
      (node (ref "IC5") (pin "43") (pinfunction "OVDD_43") (pintype "power_in"))
      (node (ref "IC5") (pin "57") (pinfunction "OVDD_57") (pintype "power_in"))
      (node (ref "IC5") (pin "6") (pinfunction "DVDD_6") (pintype "power_in"))
      (node (ref "IC5") (pin "67") (pinfunction "DVDD_67") (pintype "power_in"))
      (node (ref "IC5") (pin "78") (pinfunction "OVDD_78") (pintype "power_in"))
      (node (ref "IC5") (pin "82") (pinfunction "AVDD_82") (pintype "power_in"))
      (node (ref "IC5") (pin "84") (pinfunction "AVDD_84") (pintype "power_in"))
      (node (ref "IC5") (pin "88") (pinfunction "AVDD_88") (pintype "power_in"))
      (node (ref "IC5") (pin "95") (pinfunction "AVDD_95") (pintype "power_in"))
      (node (ref "IC5") (pin "97") (pinfunction "PVDD_97") (pintype "power_in"))
      (node (ref "IC5") (pin "99") (pinfunction "RSVD_99") (pintype "bidirectional"))
      (node (ref "IC8") (pin "1") (pinfunction "IOVCC_1") (pintype "power_in"))
      (node (ref "IC8") (pin "26") (pinfunction "IOVCC_26") (pintype "power_in"))
      (node (ref "IC8") (pin "34") (pinfunction "PLLVCC_34") (pintype "power_in"))
      (node (ref "IC8") (pin "44") (pinfunction "LVDSVCC_44") (pintype "power_in"))
      (node (ref "IC8") (pin "9") (pinfunction "VCC_9") (pintype "power_in"))
      (node (ref "JP4") (pin "1") (pinfunction "1_1") (pintype "passive"))
      (node (ref "LED1") (pin "C") (pinfunction "C_C") (pintype "passive"))
      (node (ref "R15") (pin "2") (pinfunction "P$2_2") (pintype "passive"))
      (node (ref "R18") (pin "2") (pinfunction "P$2_2") (pintype "passive"))
      (node (ref "R4") (pin "2") (pinfunction "P$2_2") (pintype "passive"))
      (node (ref "R5") (pin "2") (pinfunction "P$2_2") (pintype "passive"))
      (node (ref "R6") (pin "2") (pinfunction "P$2_2") (pintype "passive"))
    )
    (net (code "4") (name "+5V") (class "Default")
      (node (ref "C10") (pin "2") (pinfunction "P$2_2") (pintype "passive"))
      (node (ref "C23") (pin "1") (pinfunction "P$1_1") (pintype "passive"))
      (node (ref "C24") (pin "1") (pinfunction "P$1_1") (pintype "passive"))
      (node (ref "C9") (pin "1") (pinfunction "P$1_1") (pintype "passive"))
      (node (ref "CON2") (pin "18") (pinfunction "+5V_18") (pintype "bidirectional"))
      (node (ref "CON5") (pin "5") (pinfunction "VCC_5") (pintype "bidirectional"))
      (node (ref "IC4") (pin "8") (pinfunction "VCC_8") (pintype "power_in"))
      (node (ref "IC6") (pin "18") (pinfunction "AVCC_18") (pintype "power_in"))
      (node (ref "IC6") (pin "20") (pinfunction "AREF_20") (pintype "power_in"))
      (node (ref "IC6") (pin "4") (pinfunction "VCC_4") (pintype "power_in"))
      (node (ref "IC6") (pin "6") (pinfunction "VCC_6") (pintype "power_in"))
      (node (ref "JP10") (pin "2") (pinfunction "2_2") (pintype "passive"))
      (node (ref "R13") (pin "1") (pinfunction "P$1_1") (pintype "passive"))
      (node (ref "R16") (pin "1") (pinfunction "P$1_1") (pintype "passive"))
      (node (ref "R17") (pin "2") (pinfunction "P$2_2") (pintype "passive"))
      (node (ref "R19") (pin "1") (pinfunction "E_1") (pintype "passive"))
      (node (ref "R28") (pin "2") (pinfunction "P$2_2") (pintype "passive"))
      (node (ref "R29") (pin "2") (pinfunction "P$2_2") (pintype "passive"))
      (node (ref "R7") (pin "2") (pinfunction "P$2_2") (pintype "passive"))
    )
    (net (code "5") (name "+5V_USB") (class "Default")
      (node (ref "C12") (pin "1") (pinfunction "P$1_1") (pintype "passive"))
      (node (ref "CON4") (pin "1") (pinfunction "VBUS_1") (pintype "bidirectional"))
      (node (ref "IC7") (pin "19") (pinfunction "~{RESET}_19") (pintype "input"))
      (node (ref "IC7") (pin "20") (pinfunction "VCC_20") (pintype "power_in"))
      (node (ref "IC7") (pin "4") (pinfunction "VCCIO_4") (pintype "power_in"))
      (node (ref "R13") (pin "2") (pinfunction "P$2_2") (pintype "passive"))
    )
    (net (code "6") (name "+12V") (class "Default")
      (node (ref "C1") (pin "+") (pinfunction "+_+") (pintype "passive"))
      (node (ref "C34") (pin "+") (pinfunction "+_+") (pintype "passive"))
      (node (ref "CON6") (pin "28") (pinfunction "VLED_28") (pintype "bidirectional"))
      (node (ref "CON6") (pin "29") (pinfunction "VLED_29") (pintype "bidirectional"))
      (node (ref "CON6") (pin "30") (pinfunction "VLED_30") (pintype "bidirectional"))
      (node (ref "IC2") (pin "1") (pinfunction "VIN_1") (pintype "bidirectional"))
      (node (ref "LED2") (pin "C") (pinfunction "C_C") (pintype "passive"))
      (node (ref "R20") (pin "2") (pinfunction "P$2_2") (pintype "passive"))
      (node (ref "T1") (pin "2") (pinfunction "S_2") (pintype "passive"))
    )
    (net (code "9") (name "AVR_MISO") (class "Default")
      (node (ref "CON5") (pin "2") (pinfunction "MISO_2") (pintype "bidirectional"))
      (node (ref "IC6") (pin "16") (pinfunction "PB4(MISO/PCINT4)_16") (pintype "bidirectional"))
    )
    (net (code "10") (name "AVR_MOSI") (class "Default")
      (node (ref "CON5") (pin "1") (pinfunction "MOSI_1") (pintype "bidirectional"))
      (node (ref "IC6") (pin "15") (pinfunction "PB3(MOSI/OC2A/PCINT3)_15") (pintype "bidirectional"))
    )
    (net (code "11") (name "AVR_PWM") (class "Default")
      (node (ref "JP6") (pin "2") (pinfunction "2_2") (pintype "passive"))
      (node (ref "R14") (pin "2") (pinfunction "P$2_2") (pintype "passive"))
    )
    (net (code "12") (name "AVR_PWM_ADC") (class "Default")
      (node (ref "IC6") (pin "23") (pinfunction "PC0(ADC0/PCINT8)_23") (pintype "bidirectional"))
      (node (ref "R19") (pin "2") (pinfunction "S_2") (pintype "passive"))
    )
    (net (code "13") (name "AVR_SCK") (class "Default")
      (node (ref "CON5") (pin "4") (pinfunction "SCK_4") (pintype "bidirectional"))
      (node (ref "IC6") (pin "17") (pinfunction "PB5(SCK/PCINT5)_17") (pintype "bidirectional"))
    )
    (net (code "14") (name "AVR_~{RESET}") (class "Default")
      (node (ref "CON5") (pin "3") (pinfunction "RESET_3") (pintype "bidirectional"))
      (node (ref "IC6") (pin "29") (pinfunction "PC6(PCINT14/RESET)_29") (pintype "bidirectional"))
      (node (ref "JP11") (pin "2") (pinfunction "2_2") (pintype "passive"))
      (node (ref "R16") (pin "2") (pinfunction "P$2_2") (pintype "passive"))
    )
    (net (code "15") (name "EDID_SCL") (class "Default")
      (node (ref "CON2") (pin "15") (pinfunction "SCL_15") (pintype "bidirectional"))
      (node (ref "IC4") (pin "6") (pinfunction "SCL_6") (pintype "bidirectional"))
      (node (ref "IC6") (pin "28") (pinfunction "PC5(SCL/ADC5/PCINT13)_28") (pintype "bidirectional"))
      (node (ref "JP9") (pin "2") (pinfunction "2_2") (pintype "passive"))
      (node (ref "R29") (pin "1") (pinfunction "P$1_1") (pintype "passive"))
    )
    (net (code "16") (name "EDID_SDA") (class "Default")
      (node (ref "CON2") (pin "16") (pinfunction "SDA_16") (pintype "bidirectional"))
      (node (ref "IC4") (pin "5") (pinfunction "SDA_5") (pintype "bidirectional"))
      (node (ref "IC6") (pin "27") (pinfunction "PC4(SDA/ADC4/PCINT12)_27") (pintype "bidirectional"))
      (node (ref "JP9") (pin "1") (pinfunction "1_1") (pintype "passive"))
      (node (ref "R28") (pin "1") (pinfunction "P$1_1") (pintype "passive"))
    )
    (net (code "17") (name "EDID_WP") (class "Default")
      (node (ref "IC4") (pin "7") (pinfunction "WP_7") (pintype "input"))
      (node (ref "JP5") (pin "2") (pinfunction "2_2") (pintype "passive"))
      (node (ref "R17") (pin "1") (pinfunction "P$1_1") (pintype "passive"))
    )
    (net (code "18") (name "FTDI_RXD") (class "Default")
      (node (ref "IC6") (pin "31") (pinfunction "(PDPCINT17/TXD)PD1_31") (pintype "bidirectional"))
      (node (ref "IC7") (pin "5") (pinfunction "RXD_5") (pintype "input"))
    )
    (net (code "19") (name "FTDI_TXD") (class "Default")
      (node (ref "IC6") (pin "30") (pinfunction "(PCINT16/RXD)PD0_30") (pintype "bidirectional"))
      (node (ref "IC7") (pin "1") (pinfunction "TXD_1") (pintype "output"))
    )
    (net (code "20") (name "GND") (class "Default")
      (node (ref "C1") (pin "-") (pinfunction "-_-") (pintype "passive"))
      (node (ref "C10") (pin "1") (pinfunction "P$1_1") (pintype "passive"))
      (node (ref "C11") (pin "2") (pinfunction "P$2_2") (pintype "passive"))
      (node (ref "C12") (pin "2") (pinfunction "P$2_2") (pintype "passive"))
      (node (ref "C13") (pin "1") (pinfunction "P$1_1") (pintype "passive"))
      (node (ref "C14") (pin "1") (pinfunction "P$1_1") (pintype "passive"))
      (node (ref "C15") (pin "1") (pinfunction "P$1_1") (pintype "passive"))
      (node (ref "C16") (pin "1") (pinfunction "P$1_1") (pintype "passive"))
      (node (ref "C17") (pin "1") (pinfunction "P$1_1") (pintype "passive"))
      (node (ref "C18") (pin "1") (pinfunction "P$1_1") (pintype "passive"))
      (node (ref "C19") (pin "1") (pinfunction "P$1_1") (pintype "passive"))
      (node (ref "C2") (pin "-") (pinfunction "-_-") (pintype "passive"))
      (node (ref "C20") (pin "1") (pinfunction "P$1_1") (pintype "passive"))
      (node (ref "C21") (pin "1") (pinfunction "P$1_1") (pintype "passive"))
      (node (ref "C22") (pin "1") (pinfunction "P$1_1") (pintype "passive"))
      (node (ref "C23") (pin "2") (pinfunction "P$2_2") (pintype "passive"))
      (node (ref "C24") (pin "2") (pinfunction "P$2_2") (pintype "passive"))
      (node (ref "C25") (pin "1") (pinfunction "P$1_1") (pintype "passive"))
      (node (ref "C26") (pin "1") (pinfunction "P$1_1") (pintype "passive"))
      (node (ref "C27") (pin "1") (pinfunction "P$1_1") (pintype "passive"))
      (node (ref "C28") (pin "1") (pinfunction "P$1_1") (pintype "passive"))
      (node (ref "C29") (pin "1") (pinfunction "P$1_1") (pintype "passive"))
      (node (ref "C3") (pin "1") (pinfunction "P$1_1") (pintype "passive"))
      (node (ref "C30") (pin "1") (pinfunction "P$1_1") (pintype "passive"))
      (node (ref "C31") (pin "1") (pinfunction "P$1_1") (pintype "passive"))
      (node (ref "C32") (pin "1") (pinfunction "P$1_1") (pintype "passive"))
      (node (ref "C33") (pin "1") (pinfunction "P$1_1") (pintype "passive"))
      (node (ref "C34") (pin "-") (pinfunction "-_-") (pintype "passive"))
      (node (ref "C35") (pin "-") (pinfunction "-_-") (pintype "passive"))
      (node (ref "C36") (pin "-") (pinfunction "-_-") (pintype "passive"))
      (node (ref "C4") (pin "1") (pinfunction "P$1_1") (pintype "passive"))
      (node (ref "C6") (pin "1") (pinfunction "P$1_1") (pintype "passive"))
      (node (ref "C7") (pin "1") (pinfunction "P$1_1") (pintype "passive"))
      (node (ref "C8") (pin "1") (pinfunction "P$1_1") (pintype "passive"))
      (node (ref "C9") (pin "2") (pinfunction "P$2_2") (pintype "passive"))
      (node (ref "CON1") (pin "1") (pinfunction "3_1") (pintype "passive"))
      (node (ref "CON1") (pin "2") (pinfunction "2_2") (pintype "passive"))
      (node (ref "CON2") (pin "11") (pinfunction "CLKS_11") (pintype "bidirectional"))
      (node (ref "CON2") (pin "17") (pinfunction "GND_17") (pintype "bidirectional"))
      (node (ref "CON2") (pin "2") (pinfunction "DATA2S_2") (pintype "bidirectional"))
      (node (ref "CON2") (pin "5") (pinfunction "DATA1S_5") (pintype "bidirectional"))
      (node (ref "CON2") (pin "8") (pinfunction "DATA0S_8") (pintype "bidirectional"))
      (node (ref "CON2") (pin "GND@1") (pinfunction "GND_GND@1") (pintype "power_in"))
      (node (ref "CON2") (pin "GND@2") (pinfunction "GND_GND@2") (pintype "power_in"))
      (node (ref "CON2") (pin "GND@3") (pinfunction "GND_GND@3") (pintype "power_in"))
      (node (ref "CON2") (pin "GND@4") (pinfunction "GND_GND@4") (pintype "power_in"))
      (node (ref "CON3") (pin "1") (pinfunction "LED-K_1") (pintype "bidirectional"))
      (node (ref "CON3") (pin "29") (pinfunction "GND_29") (pintype "bidirectional"))
      (node (ref "CON3") (pin "3") (pinfunction "GND_3") (pintype "bidirectional"))
      (node (ref "CON3") (pin "36") (pinfunction "GND_36") (pintype "bidirectional"))
      (node (ref "CON3") (pin "GND@1") (pinfunction "GND_GND@1") (pintype "power_in"))
      (node (ref "CON3") (pin "GND@2") (pinfunction "GND_GND@2") (pintype "power_in"))
      (node (ref "CON4") (pin "5") (pinfunction "GND_5") (pintype "bidirectional"))
      (node (ref "CON4") (pin "GND@1") (pinfunction "GND_GND@1") (pintype "power_in"))
      (node (ref "CON4") (pin "GND@2") (pinfunction "GND_GND@2") (pintype "power_in"))
      (node (ref "CON4") (pin "GND@3") (pinfunction "GND_GND@3") (pintype "power_in"))
      (node (ref "CON4") (pin "GND@4") (pinfunction "GND_GND@4") (pintype "power_in"))
      (node (ref "CON5") (pin "6") (pinfunction "GND_6") (pintype "bidirectional"))
      (node (ref "CON5") (pin "GND@1") (pinfunction "GND_GND@1") (pintype "power_in"))
      (node (ref "CON5") (pin "GND@2") (pinfunction "GND_GND@2") (pintype "power_in"))
      (node (ref "CON6") (pin "12") (pinfunction "GND_12") (pintype "bidirectional"))
      (node (ref "CON6") (pin "15") (pinfunction "GND_15") (pintype "bidirectional"))
      (node (ref "CON6") (pin "18") (pinfunction "GND_18") (pintype "bidirectional"))
      (node (ref "CON6") (pin "21") (pinfunction "GND_21") (pintype "bidirectional"))
      (node (ref "CON6") (pin "26") (pinfunction "GND_26") (pintype "bidirectional"))
      (node (ref "CON6") (pin "3") (pinfunction "GND_3") (pintype "bidirectional"))
      (node (ref "CON6") (pin "4") (pinfunction "GND_4") (pintype "bidirectional"))
      (node (ref "CON6") (pin "6") (pinfunction "GND_6") (pintype "bidirectional"))
      (node (ref "CON6") (pin "9") (pinfunction "GND_9") (pintype "bidirectional"))
      (node (ref "CON6") (pin "GND@1") (pinfunction "GND_GND@1") (pintype "power_in"))
      (node (ref "CON6") (pin "GND@2") (pinfunction "GND_GND@2") (pintype "power_in"))
      (node (ref "CON6") (pin "GND@3") (pinfunction "GND_GND@3") (pintype "power_in"))
      (node (ref "CON6") (pin "GND@4") (pinfunction "GND_GND@4") (pintype "power_in"))
      (node (ref "IC2") (pin "2") (pinfunction "GND_2") (pintype "bidirectional"))
      (node (ref "IC2") (pin "6") (pinfunction "PGND_6") (pintype "bidirectional"))
      (node (ref "IC4") (pin "1") (pinfunction "A0_1") (pintype "input"))
      (node (ref "IC4") (pin "2") (pinfunction "A1_2") (pintype "input"))
      (node (ref "IC4") (pin "3") (pinfunction "A2_3") (pintype "input"))
      (node (ref "IC4") (pin "4") (pinfunction "GND_4") (pintype "power_in"))
      (node (ref "IC5") (pin "1") (pinfunction "DFO_1") (pintype "bidirectional"))
      (node (ref "IC5") (pin "19") (pinfunction "OGND_19") (pintype "power_in"))
      (node (ref "IC5") (pin "28") (pinfunction "OGND_28") (pintype "power_in"))
      (node (ref "IC5") (pin "3") (pinfunction "ST_3") (pintype "bidirectional"))
      (node (ref "IC5") (pin "39") (pinfunction "DGND_39") (pintype "power_in"))
      (node (ref "IC5") (pin "45") (pinfunction "OGND_45") (pintype "power_in"))
      (node (ref "IC5") (pin "5") (pinfunction "DGND_5") (pintype "power_in"))
      (node (ref "IC5") (pin "58") (pinfunction "OGND_58") (pintype "power_in"))
      (node (ref "IC5") (pin "68") (pinfunction "DGND_68") (pintype "power_in"))
      (node (ref "IC5") (pin "7") (pinfunction "~{STAG}_7") (pintype "bidirectional"))
      (node (ref "IC5") (pin "76") (pinfunction "OGND_76") (pintype "power_in"))
      (node (ref "IC5") (pin "79") (pinfunction "AGND_79") (pintype "power_in"))
      (node (ref "IC5") (pin "83") (pinfunction "AGND_83") (pintype "power_in"))
      (node (ref "IC5") (pin "87") (pinfunction "AGND_87") (pintype "power_in"))
      (node (ref "IC5") (pin "89") (pinfunction "AGND_89") (pintype "power_in"))
      (node (ref "IC5") (pin "92") (pinfunction "AGND_92") (pintype "power_in"))
      (node (ref "IC5") (pin "98") (pinfunction "PGND_98") (pintype "power_in"))
      (node (ref "IC6") (pin "21") (pinfunction "GND_21") (pintype "power_in"))
      (node (ref "IC6") (pin "3") (pinfunction "GND_3") (pintype "power_in"))
      (node (ref "IC6") (pin "5") (pinfunction "GND_5") (pintype "power_in"))
      (node (ref "IC7") (pin "18") (pinfunction "GND_18") (pintype "power_in"))
      (node (ref "IC7") (pin "21") (pinfunction "GND_21") (pintype "power_in"))
      (node (ref "IC7") (pin "25") (pinfunction "GND_25") (pintype "power_in"))
      (node (ref "IC7") (pin "26") (pinfunction "TEST_26") (pintype "input"))
      (node (ref "IC7") (pin "7") (pinfunction "GND_7") (pintype "power_in"))
      (node (ref "IC8") (pin "13") (pinfunction "GND_13") (pintype "power_in"))
      (node (ref "IC8") (pin "21") (pinfunction "GND_21") (pintype "power_in"))
      (node (ref "IC8") (pin "25") (pinfunction "D23_25") (pintype "bidirectional"))
      (node (ref "IC8") (pin "29") (pinfunction "GND_29") (pintype "power_in"))
      (node (ref "IC8") (pin "33") (pinfunction "GND_33") (pintype "power_in"))
      (node (ref "IC8") (pin "35") (pinfunction "GND_35") (pintype "power_in"))
      (node (ref "IC8") (pin "36") (pinfunction "GND_36") (pintype "power_in"))
      (node (ref "IC8") (pin "43") (pinfunction "GND_43") (pintype "power_in"))
      (node (ref "IC8") (pin "49") (pinfunction "GND_49") (pintype "power_in"))
      (node (ref "IC8") (pin "5") (pinfunction "GND_5") (pintype "power_in"))
      (node (ref "IC8") (pin "53") (pinfunction "GND_53") (pintype "power_in"))
      (node (ref "JP1") (pin "1") (pinfunction "1_1") (pintype "passive"))
      (node (ref "JP10") (pin "1") (pinfunction "1_1") (pintype "passive"))
      (node (ref "JP11") (pin "1") (pinfunction "1_1") (pintype "passive"))
      (node (ref "JP2") (pin "1") (pinfunction "1_1") (pintype "passive"))
      (node (ref "JP3") (pin "1") (pinfunction "1_1") (pintype "passive"))
      (node (ref "JP5") (pin "1") (pinfunction "1_1") (pintype "passive"))
      (node (ref "JP7") (pin "1") (pinfunction "1_1") (pintype "passive"))
      (node (ref "JP8") (pin "1") (pinfunction "1_1") (pintype "passive"))
      (node (ref "R1") (pin "1") (pinfunction "P$1_1") (pintype "passive"))
      (node (ref "R19") (pin "3") (pinfunction "A_3") (pintype "passive"))
      (node (ref "R25") (pin "1") (pinfunction "P$1_1") (pintype "passive"))
      (node (ref "R27") (pin "1") (pinfunction "P$1_1") (pintype "passive"))
    )
    (net (code "21") (name "HDMI_CLK_N") (class "Default")
      (node (ref "CON2") (pin "12") (pinfunction "CLK-_12") (pintype "bidirectional"))
      (node (ref "IC5") (pin "94") (pinfunction "RXC-_94") (pintype "bidirectional"))
    )
    (net (code "22") (name "HDMI_CLK_P") (class "Default")
      (node (ref "CON2") (pin "10") (pinfunction "CLK+_10") (pintype "bidirectional"))
      (node (ref "IC5") (pin "93") (pinfunction "RXC+_93") (pintype "bidirectional"))
    )
    (net (code "23") (name "HDMI_DAT0_N") (class "Default")
      (node (ref "CON2") (pin "9") (pinfunction "DATA0-_9") (pintype "bidirectional"))
      (node (ref "IC5") (pin "91") (pinfunction "RX0-_91") (pintype "bidirectional"))
    )
    (net (code "24") (name "HDMI_DAT0_P") (class "Default")
      (node (ref "CON2") (pin "7") (pinfunction "DATA0+_7") (pintype "bidirectional"))
      (node (ref "IC5") (pin "90") (pinfunction "RX0+_90") (pintype "bidirectional"))
    )
    (net (code "25") (name "HDMI_DAT1_N") (class "Default")
      (node (ref "CON2") (pin "6") (pinfunction "DATA1-_6") (pintype "bidirectional"))
      (node (ref "IC5") (pin "86") (pinfunction "RX1-_86") (pintype "bidirectional"))
    )
    (net (code "26") (name "HDMI_DAT1_P") (class "Default")
      (node (ref "CON2") (pin "4") (pinfunction "DATA1+_4") (pintype "bidirectional"))
      (node (ref "IC5") (pin "85") (pinfunction "RX1+_85") (pintype "bidirectional"))
    )
    (net (code "27") (name "HDMI_DAT2_N") (class "Default")
      (node (ref "CON2") (pin "3") (pinfunction "DATA2-_3") (pintype "bidirectional"))
      (node (ref "IC5") (pin "81") (pinfunction "RX2-_81") (pintype "bidirectional"))
    )
    (net (code "28") (name "HDMI_DAT2_P") (class "Default")
      (node (ref "CON2") (pin "1") (pinfunction "DATA2+_1") (pintype "bidirectional"))
      (node (ref "IC5") (pin "80") (pinfunction "RX2+_80") (pintype "bidirectional"))
    )
    (net (code "29") (name "HDMI_OCK_INV") (class "Default")
      (node (ref "IC5") (pin "100") (pinfunction "OCK_INV_100") (pintype "bidirectional"))
      (node (ref "JP1") (pin "2") (pinfunction "2_2") (pintype "passive"))
      (node (ref "R6") (pin "1") (pinfunction "P$1_1") (pintype "passive"))
    )
    (net (code "30") (name "HDMI_PIXS") (class "Default")
      (node (ref "IC5") (pin "4") (pinfunction "PIXS_4") (pintype "bidirectional"))
      (node (ref "JP2") (pin "2") (pinfunction "2_2") (pintype "passive"))
      (node (ref "R5") (pin "1") (pinfunction "P$1_1") (pintype "passive"))
    )
    (net (code "31") (name "LVDS_0_N") (class "Default")
      (node (ref "CON6") (pin "7") (pinfunction "RA-_7") (pintype "bidirectional"))
      (node (ref "IC8") (pin "48") (pinfunction "Y0M_48") (pintype "bidirectional"))
    )
    (net (code "32") (name "LVDS_0_P") (class "Default")
      (node (ref "CON6") (pin "8") (pinfunction "RA+_8") (pintype "bidirectional"))
      (node (ref "IC8") (pin "47") (pinfunction "Y0P_47") (pintype "bidirectional"))
    )
    (net (code "33") (name "LVDS_1_N") (class "Default")
      (node (ref "CON6") (pin "10") (pinfunction "RB-_10") (pintype "bidirectional"))
      (node (ref "IC8") (pin "46") (pinfunction "Y1M_46") (pintype "bidirectional"))
    )
    (net (code "34") (name "LVDS_1_P") (class "Default")
      (node (ref "CON6") (pin "11") (pinfunction "RB+_11") (pintype "bidirectional"))
      (node (ref "IC8") (pin "45") (pinfunction "Y1P_45") (pintype "bidirectional"))
    )
    (net (code "35") (name "LVDS_2_N") (class "Default")
      (node (ref "CON6") (pin "13") (pinfunction "RC-_13") (pintype "bidirectional"))
      (node (ref "IC8") (pin "42") (pinfunction "Y2M_42") (pintype "bidirectional"))
    )
    (net (code "36") (name "LVDS_2_P") (class "Default")
      (node (ref "CON6") (pin "14") (pinfunction "RC+_14") (pintype "bidirectional"))
      (node (ref "IC8") (pin "41") (pinfunction "Y2P_41") (pintype "bidirectional"))
    )
    (net (code "37") (name "LVDS_3_N") (class "Default")
      (node (ref "CON6") (pin "19") (pinfunction "RDM-_19") (pintype "bidirectional"))
      (node (ref "IC8") (pin "38") (pinfunction "Y3M_38") (pintype "bidirectional"))
    )
    (net (code "38") (name "LVDS_3_P") (class "Default")
      (node (ref "CON6") (pin "20") (pinfunction "RDM+_20") (pintype "bidirectional"))
      (node (ref "IC8") (pin "37") (pinfunction "Y3P_37") (pintype "bidirectional"))
    )
    (net (code "39") (name "LVDS_CLK_N") (class "Default")
      (node (ref "CON6") (pin "16") (pinfunction "RCLK-_16") (pintype "bidirectional"))
      (node (ref "IC8") (pin "40") (pinfunction "CLKOUTM_40") (pintype "bidirectional"))
    )
    (net (code "40") (name "LVDS_CLK_P") (class "Default")
      (node (ref "CON6") (pin "17") (pinfunction "RCLK+_17") (pintype "bidirectional"))
      (node (ref "IC8") (pin "39") (pinfunction "CLKOUTP_39") (pintype "bidirectional"))
    )
    (net (code "41") (name "LVDS_LED_EN") (class "Default")
      (node (ref "CON6") (pin "25") (pinfunction "LED_EN_25") (pintype "bidirectional"))
      (node (ref "JP8") (pin "2") (pinfunction "2_2") (pintype "passive"))
      (node (ref "R4") (pin "1") (pinfunction "P$1_1") (pintype "passive"))
    )
    (net (code "42") (name "LVDS_PWM") (class "Default")
      (node (ref "CON6") (pin "24") (pinfunction "PWM_24") (pintype "bidirectional"))
      (node (ref "JP6") (pin "3") (pinfunction "3_3") (pintype "passive"))
    )
    (net (code "43") (name "LVDS_REVSCAN") (class "Default")
      (node (ref "CON6") (pin "5") (pinfunction "SHLI_5") (pintype "bidirectional"))
      (node (ref "JP7") (pin "2") (pinfunction "2_2") (pintype "passive"))
      (node (ref "R18") (pin "1") (pinfunction "P$1_1") (pintype "passive"))
    )
    (net (code "44") (name "Net-(C7-P$2)") (class "Default")
      (node (ref "C7") (pin "2") (pinfunction "P$2_2") (pintype "passive"))
      (node (ref "IC6") (pin "7") (pinfunction "PB6(PCINT6/XTAL1/TOSC1)_7") (pintype "bidirectional"))
      (node (ref "Q1") (pin "2") (pinfunction "2_2") (pintype "passive"))
    )
    (net (code "45") (name "Net-(C8-P$2)") (class "Default")
      (node (ref "C8") (pin "2") (pinfunction "P$2_2") (pintype "passive"))
      (node (ref "IC6") (pin "8") (pinfunction "PB7(PCINT7/XTAL2/TOSC2)_8") (pintype "bidirectional"))
      (node (ref "Q1") (pin "1") (pinfunction "1_1") (pintype "passive"))
    )
    (net (code "46") (name "Net-(C11-P$1)") (class "Default")
      (node (ref "C11") (pin "1") (pinfunction "P$1_1") (pintype "passive"))
      (node (ref "IC7") (pin "17") (pinfunction "3V3OUT_17") (pintype "output"))
    )
    (net (code "47") (name "Net-(CON1-1)") (class "Default")
      (node (ref "CON1") (pin "3") (pinfunction "1_3") (pintype "passive"))
      (node (ref "T1") (pin "3") (pinfunction "D_3") (pintype "passive"))
    )
    (net (code "48") (name "Net-(CON2-DETECT)") (class "Default")
      (node (ref "CON2") (pin "19") (pinfunction "DETECT_19") (pintype "bidirectional"))
      (node (ref "R7") (pin "1") (pinfunction "P$1_1") (pintype "passive"))
    )
    (net (code "49") (name "Net-(CON3-LED-A)") (class "Default")
      (node (ref "CON3") (pin "2") (pinfunction "LED-A_2") (pintype "bidirectional"))
      (node (ref "T2") (pin "2") (pinfunction "S_2") (pintype "passive"))
    )
    (net (code "50") (name "Net-(IC5-DE)") (class "Default")
      (node (ref "IC5") (pin "46") (pinfunction "DE_46") (pintype "bidirectional"))
      (node (ref "R2") (pin "3M") (pinfunction "3M_3M") (pintype "bidirectional"))
    )
    (net (code "51") (name "Net-(IC5-HSYNC)") (class "Default")
      (node (ref "IC5") (pin "48") (pinfunction "HSYNC_48") (pintype "bidirectional"))
      (node (ref "R2") (pin "1M") (pinfunction "1M_1M") (pintype "bidirectional"))
    )
    (net (code "52") (name "Net-(IC5-ODCK)") (class "Default")
      (node (ref "IC5") (pin "44") (pinfunction "ODCK_44") (pintype "bidirectional"))
      (node (ref "R2") (pin "4M") (pinfunction "4M_4M") (pintype "bidirectional"))
    )
    (net (code "53") (name "Net-(IC5-QE0)") (class "Default")
      (node (ref "IC5") (pin "10") (pinfunction "QE0_10") (pintype "bidirectional"))
      (node (ref "R3") (pin "4M") (pinfunction "4M_4M") (pintype "bidirectional"))
    )
    (net (code "54") (name "Net-(IC5-QE1)") (class "Default")
      (node (ref "IC5") (pin "11") (pinfunction "QE1_11") (pintype "bidirectional"))
      (node (ref "R3") (pin "3M") (pinfunction "3M_3M") (pintype "bidirectional"))
    )
    (net (code "55") (name "Net-(IC5-QE2)") (class "Default")
      (node (ref "IC5") (pin "12") (pinfunction "QE2_12") (pintype "bidirectional"))
      (node (ref "R3") (pin "2M") (pinfunction "2M_2M") (pintype "bidirectional"))
    )
    (net (code "56") (name "Net-(IC5-QE3)") (class "Default")
      (node (ref "IC5") (pin "13") (pinfunction "QE3_13") (pintype "bidirectional"))
      (node (ref "R3") (pin "1M") (pinfunction "1M_1M") (pintype "bidirectional"))
    )
    (net (code "57") (name "Net-(IC5-QE4)") (class "Default")
      (node (ref "IC5") (pin "14") (pinfunction "QE4_14") (pintype "bidirectional"))
      (node (ref "R8") (pin "4M") (pinfunction "4M_4M") (pintype "bidirectional"))
    )
    (net (code "58") (name "Net-(IC5-QE5)") (class "Default")
      (node (ref "IC5") (pin "15") (pinfunction "QE5_15") (pintype "bidirectional"))
      (node (ref "R8") (pin "3M") (pinfunction "3M_3M") (pintype "bidirectional"))
    )
    (net (code "59") (name "Net-(IC5-QE6)") (class "Default")
      (node (ref "IC5") (pin "16") (pinfunction "QE6_16") (pintype "bidirectional"))
      (node (ref "R8") (pin "2M") (pinfunction "2M_2M") (pintype "bidirectional"))
    )
    (net (code "60") (name "Net-(IC5-QE7)") (class "Default")
      (node (ref "IC5") (pin "17") (pinfunction "QE7_17") (pintype "bidirectional"))
      (node (ref "R8") (pin "1M") (pinfunction "1M_1M") (pintype "bidirectional"))
    )
    (net (code "61") (name "Net-(IC5-QE8)") (class "Default")
      (node (ref "IC5") (pin "20") (pinfunction "QE8_20") (pintype "bidirectional"))
      (node (ref "R9") (pin "4M") (pinfunction "4M_4M") (pintype "bidirectional"))
    )
    (net (code "62") (name "Net-(IC5-QE9)") (class "Default")
      (node (ref "IC5") (pin "21") (pinfunction "QE9_21") (pintype "bidirectional"))
      (node (ref "R9") (pin "3M") (pinfunction "3M_3M") (pintype "bidirectional"))
    )
    (net (code "63") (name "Net-(IC5-QE10)") (class "Default")
      (node (ref "IC5") (pin "22") (pinfunction "QE10_22") (pintype "bidirectional"))
      (node (ref "R9") (pin "2M") (pinfunction "2M_2M") (pintype "bidirectional"))
    )
    (net (code "64") (name "Net-(IC5-QE11)") (class "Default")
      (node (ref "IC5") (pin "23") (pinfunction "QE11_23") (pintype "bidirectional"))
      (node (ref "R9") (pin "1M") (pinfunction "1M_1M") (pintype "bidirectional"))
    )
    (net (code "65") (name "Net-(IC5-QE12)") (class "Default")
      (node (ref "IC5") (pin "24") (pinfunction "QE12_24") (pintype "bidirectional"))
      (node (ref "R10") (pin "4M") (pinfunction "4M_4M") (pintype "bidirectional"))
    )
    (net (code "66") (name "Net-(IC5-QE13)") (class "Default")
      (node (ref "IC5") (pin "25") (pinfunction "QE13_25") (pintype "bidirectional"))
      (node (ref "R10") (pin "3M") (pinfunction "3M_3M") (pintype "bidirectional"))
    )
    (net (code "67") (name "Net-(IC5-QE14)") (class "Default")
      (node (ref "IC5") (pin "26") (pinfunction "QE14_26") (pintype "bidirectional"))
      (node (ref "R10") (pin "2M") (pinfunction "2M_2M") (pintype "bidirectional"))
    )
    (net (code "68") (name "Net-(IC5-QE15)") (class "Default")
      (node (ref "IC5") (pin "27") (pinfunction "QE15_27") (pintype "bidirectional"))
      (node (ref "R10") (pin "1M") (pinfunction "1M_1M") (pintype "bidirectional"))
    )
    (net (code "69") (name "Net-(IC5-QE16)") (class "Default")
      (node (ref "IC5") (pin "30") (pinfunction "QE16_30") (pintype "bidirectional"))
      (node (ref "R11") (pin "4M") (pinfunction "4M_4M") (pintype "bidirectional"))
    )
    (net (code "70") (name "Net-(IC5-QE17)") (class "Default")
      (node (ref "IC5") (pin "31") (pinfunction "QE17_31") (pintype "bidirectional"))
      (node (ref "R11") (pin "3M") (pinfunction "3M_3M") (pintype "bidirectional"))
    )
    (net (code "71") (name "Net-(IC5-QE18)") (class "Default")
      (node (ref "IC5") (pin "32") (pinfunction "QE18_32") (pintype "bidirectional"))
      (node (ref "R11") (pin "2M") (pinfunction "2M_2M") (pintype "bidirectional"))
    )
    (net (code "72") (name "Net-(IC5-QE19)") (class "Default")
      (node (ref "IC5") (pin "33") (pinfunction "QE19_33") (pintype "bidirectional"))
      (node (ref "R11") (pin "1M") (pinfunction "1M_1M") (pintype "bidirectional"))
    )
    (net (code "73") (name "Net-(IC5-QE20)") (class "Default")
      (node (ref "IC5") (pin "34") (pinfunction "QE20_34") (pintype "bidirectional"))
      (node (ref "R12") (pin "4M") (pinfunction "4M_4M") (pintype "bidirectional"))
    )
    (net (code "74") (name "Net-(IC5-QE21)") (class "Default")
      (node (ref "IC5") (pin "35") (pinfunction "QE21_35") (pintype "bidirectional"))
      (node (ref "R12") (pin "3M") (pinfunction "3M_3M") (pintype "bidirectional"))
    )
    (net (code "75") (name "Net-(IC5-QE22)") (class "Default")
      (node (ref "IC5") (pin "36") (pinfunction "QE22_36") (pintype "bidirectional"))
      (node (ref "R12") (pin "2M") (pinfunction "2M_2M") (pintype "bidirectional"))
    )
    (net (code "76") (name "Net-(IC5-QE23)") (class "Default")
      (node (ref "IC5") (pin "37") (pinfunction "QE23_37") (pintype "bidirectional"))
      (node (ref "R12") (pin "1M") (pinfunction "1M_1M") (pintype "bidirectional"))
    )
    (net (code "77") (name "Net-(IC5-VSYNC)") (class "Default")
      (node (ref "IC5") (pin "47") (pinfunction "VSYNC_47") (pintype "bidirectional"))
      (node (ref "R2") (pin "2M") (pinfunction "2M_2M") (pintype "bidirectional"))
    )
    (net (code "78") (name "Net-(IC6-PB1(OC1A{slash}PCINT1))") (class "Default")
      (node (ref "IC6") (pin "13") (pinfunction "PB1(OC1A/PCINT1)_13") (pintype "bidirectional"))
      (node (ref "R14") (pin "1") (pinfunction "P$1_1") (pintype "passive"))
    )
    (net (code "79") (name "Net-(IC7-USBDM)") (class "Default")
      (node (ref "IC7") (pin "16") (pinfunction "USBDM_16") (pintype "bidirectional"))
      (node (ref "R23") (pin "2") (pinfunction "P$2_2") (pintype "passive"))
    )
    (net (code "80") (name "Net-(IC7-USBDP)") (class "Default")
      (node (ref "IC7") (pin "15") (pinfunction "USBDP_15") (pintype "bidirectional"))
      (node (ref "R22") (pin "2") (pinfunction "P$2_2") (pintype "passive"))
    )
    (net (code "81") (name "Net-(R1-P$2)") (class "Default")
      (node (ref "R1") (pin "2") (pinfunction "P$2_2") (pintype "passive"))
      (node (ref "T1") (pin "1") (pinfunction "G_1") (pintype "passive"))
    )
    (net (code "82") (name "Net-(R20-P$1)") (class "Default")
      (node (ref "R20") (pin "1") (pinfunction "P$1_1") (pintype "passive"))
      (node (ref "T2") (pin "3") (pinfunction "D_3") (pintype "passive"))
    )
    (net (code "83") (name "Net-(R25-P$2)") (class "Default")
      (node (ref "LED1") (pin "A") (pinfunction "A_A") (pintype "passive"))
      (node (ref "R25") (pin "2") (pinfunction "P$2_2") (pintype "passive"))
    )
    (net (code "84") (name "Net-(R27-P$2)") (class "Default")
      (node (ref "LED2") (pin "A") (pinfunction "A_A") (pintype "passive"))
      (node (ref "R27") (pin "2") (pinfunction "P$2_2") (pintype "passive"))
    )
    (net (code "85") (name "RGB_DE") (class "Default")
      (node (ref "CON3") (pin "34") (pinfunction "DEN_34") (pintype "bidirectional"))
      (node (ref "IC8") (pin "30") (pinfunction "D26_30") (pintype "bidirectional"))
      (node (ref "R2") (pin "3P") (pinfunction "3P_3P") (pintype "bidirectional"))
    )
    (net (code "86") (name "RGB_DISP") (class "Default")
      (node (ref "CON3") (pin "31") (pinfunction "DISP_31") (pintype "bidirectional"))
      (node (ref "JP3") (pin "2") (pinfunction "2_2") (pintype "passive"))
      (node (ref "R15") (pin "1") (pinfunction "P$1_1") (pintype "passive"))
    )
    (net (code "87") (name "RGB_EVEN_B0") (class "Default")
      (node (ref "CON3") (pin "21") (pinfunction "B0_21") (pintype "bidirectional"))
      (node (ref "IC8") (pin "15") (pinfunction "D15_15") (pintype "bidirectional"))
      (node (ref "R3") (pin "4P") (pinfunction "4P_4P") (pintype "bidirectional"))
    )
    (net (code "88") (name "RGB_EVEN_B1") (class "Default")
      (node (ref "CON3") (pin "22") (pinfunction "B1_22") (pintype "bidirectional"))
      (node (ref "IC8") (pin "19") (pinfunction "D18_19") (pintype "bidirectional"))
      (node (ref "R3") (pin "3P") (pinfunction "3P_3P") (pintype "bidirectional"))
    )
    (net (code "89") (name "RGB_EVEN_B2") (class "Default")
      (node (ref "CON3") (pin "23") (pinfunction "B2_23") (pintype "bidirectional"))
      (node (ref "IC8") (pin "20") (pinfunction "D19_20") (pintype "bidirectional"))
      (node (ref "R3") (pin "2P") (pinfunction "2P_2P") (pintype "bidirectional"))
    )
    (net (code "90") (name "RGB_EVEN_B3") (class "Default")
      (node (ref "CON3") (pin "24") (pinfunction "B3_24") (pintype "bidirectional"))
      (node (ref "IC8") (pin "22") (pinfunction "D20_22") (pintype "bidirectional"))
      (node (ref "R3") (pin "1P") (pinfunction "1P_1P") (pintype "bidirectional"))
    )
    (net (code "91") (name "RGB_EVEN_B4") (class "Default")
      (node (ref "CON3") (pin "25") (pinfunction "B4_25") (pintype "bidirectional"))
      (node (ref "IC8") (pin "23") (pinfunction "D21_23") (pintype "bidirectional"))
      (node (ref "R8") (pin "4P") (pinfunction "4P_4P") (pintype "bidirectional"))
    )
    (net (code "92") (name "RGB_EVEN_B5") (class "Default")
      (node (ref "CON3") (pin "26") (pinfunction "B5_26") (pintype "bidirectional"))
      (node (ref "IC8") (pin "24") (pinfunction "D22_24") (pintype "bidirectional"))
      (node (ref "R8") (pin "3P") (pinfunction "3P_3P") (pintype "bidirectional"))
    )
    (net (code "93") (name "RGB_EVEN_B6") (class "Default")
      (node (ref "CON3") (pin "27") (pinfunction "B6_27") (pintype "bidirectional"))
      (node (ref "IC8") (pin "16") (pinfunction "D16_16") (pintype "bidirectional"))
      (node (ref "R8") (pin "2P") (pinfunction "2P_2P") (pintype "bidirectional"))
    )
    (net (code "94") (name "RGB_EVEN_B7") (class "Default")
      (node (ref "CON3") (pin "28") (pinfunction "B7_28") (pintype "bidirectional"))
      (node (ref "IC8") (pin "18") (pinfunction "D17_18") (pintype "bidirectional"))
      (node (ref "R8") (pin "1P") (pinfunction "1P_1P") (pintype "bidirectional"))
    )
    (net (code "95") (name "RGB_EVEN_G0") (class "Default")
      (node (ref "CON3") (pin "13") (pinfunction "G0_13") (pintype "bidirectional"))
      (node (ref "IC8") (pin "4") (pinfunction "D7_4") (pintype "bidirectional"))
      (node (ref "R9") (pin "4P") (pinfunction "4P_4P") (pintype "bidirectional"))
    )
    (net (code "96") (name "RGB_EVEN_G1") (class "Default")
      (node (ref "CON3") (pin "14") (pinfunction "G1_14") (pintype "bidirectional"))
      (node (ref "IC8") (pin "6") (pinfunction "D8_6") (pintype "bidirectional"))
      (node (ref "R9") (pin "3P") (pinfunction "3P_3P") (pintype "bidirectional"))
    )
    (net (code "97") (name "RGB_EVEN_G2") (class "Default")
      (node (ref "CON3") (pin "15") (pinfunction "G2_15") (pintype "bidirectional"))
      (node (ref "IC8") (pin "7") (pinfunction "D9_7") (pintype "bidirectional"))
      (node (ref "R9") (pin "2P") (pinfunction "2P_2P") (pintype "bidirectional"))
    )
    (net (code "98") (name "RGB_EVEN_G3") (class "Default")
      (node (ref "CON3") (pin "16") (pinfunction "G3_16") (pintype "bidirectional"))
      (node (ref "IC8") (pin "11") (pinfunction "D12_11") (pintype "bidirectional"))
      (node (ref "R9") (pin "1P") (pinfunction "1P_1P") (pintype "bidirectional"))
    )
    (net (code "99") (name "RGB_EVEN_G4") (class "Default")
      (node (ref "CON3") (pin "17") (pinfunction "G4_17") (pintype "bidirectional"))
      (node (ref "IC8") (pin "12") (pinfunction "D13_12") (pintype "bidirectional"))
      (node (ref "R10") (pin "4P") (pinfunction "4P_4P") (pintype "bidirectional"))
    )
    (net (code "100") (name "RGB_EVEN_G5") (class "Default")
      (node (ref "CON3") (pin "18") (pinfunction "G5_18") (pintype "bidirectional"))
      (node (ref "IC8") (pin "14") (pinfunction "D14_14") (pintype "bidirectional"))
      (node (ref "R10") (pin "3P") (pinfunction "3P_3P") (pintype "bidirectional"))
    )
    (net (code "101") (name "RGB_EVEN_G6") (class "Default")
      (node (ref "CON3") (pin "19") (pinfunction "G6_19") (pintype "bidirectional"))
      (node (ref "IC8") (pin "8") (pinfunction "D10_8") (pintype "bidirectional"))
      (node (ref "R10") (pin "2P") (pinfunction "2P_2P") (pintype "bidirectional"))
    )
    (net (code "102") (name "RGB_EVEN_G7") (class "Default")
      (node (ref "CON3") (pin "20") (pinfunction "G7_20") (pintype "bidirectional"))
      (node (ref "IC8") (pin "10") (pinfunction "D11_10") (pintype "bidirectional"))
      (node (ref "R10") (pin "1P") (pinfunction "1P_1P") (pintype "bidirectional"))
    )
    (net (code "103") (name "RGB_EVEN_R0") (class "Default")
      (node (ref "CON3") (pin "5") (pinfunction "R0_5") (pintype "bidirectional"))
      (node (ref "IC8") (pin "51") (pinfunction "D0_51") (pintype "bidirectional"))
      (node (ref "R11") (pin "4P") (pinfunction "4P_4P") (pintype "bidirectional"))
    )
    (net (code "104") (name "RGB_EVEN_R1") (class "Default")
      (node (ref "CON3") (pin "6") (pinfunction "R1_6") (pintype "bidirectional"))
      (node (ref "IC8") (pin "52") (pinfunction "D1_52") (pintype "bidirectional"))
      (node (ref "R11") (pin "3P") (pinfunction "3P_3P") (pintype "bidirectional"))
    )
    (net (code "105") (name "RGB_EVEN_R2") (class "Default")
      (node (ref "CON3") (pin "7") (pinfunction "R2_7") (pintype "bidirectional"))
      (node (ref "IC8") (pin "54") (pinfunction "D2_54") (pintype "bidirectional"))
      (node (ref "R11") (pin "2P") (pinfunction "2P_2P") (pintype "bidirectional"))
    )
    (net (code "106") (name "RGB_EVEN_R3") (class "Default")
      (node (ref "CON3") (pin "8") (pinfunction "R3_8") (pintype "bidirectional"))
      (node (ref "IC8") (pin "55") (pinfunction "D3_55") (pintype "bidirectional"))
      (node (ref "R11") (pin "1P") (pinfunction "1P_1P") (pintype "bidirectional"))
    )
    (net (code "107") (name "RGB_EVEN_R4") (class "Default")
      (node (ref "CON3") (pin "9") (pinfunction "R4_9") (pintype "bidirectional"))
      (node (ref "IC8") (pin "56") (pinfunction "D4_56") (pintype "bidirectional"))
      (node (ref "R12") (pin "4P") (pinfunction "4P_4P") (pintype "bidirectional"))
    )
    (net (code "108") (name "RGB_EVEN_R5") (class "Default")
      (node (ref "CON3") (pin "10") (pinfunction "R5_10") (pintype "bidirectional"))
      (node (ref "IC8") (pin "3") (pinfunction "D6_3") (pintype "bidirectional"))
      (node (ref "R12") (pin "3P") (pinfunction "3P_3P") (pintype "bidirectional"))
    )
    (net (code "109") (name "RGB_EVEN_R6") (class "Default")
      (node (ref "CON3") (pin "11") (pinfunction "R6_11") (pintype "bidirectional"))
      (node (ref "IC8") (pin "50") (pinfunction "D27_50") (pintype "bidirectional"))
      (node (ref "R12") (pin "2P") (pinfunction "2P_2P") (pintype "bidirectional"))
    )
    (net (code "110") (name "RGB_EVEN_R7") (class "Default")
      (node (ref "CON3") (pin "12") (pinfunction "R7_12") (pintype "bidirectional"))
      (node (ref "IC8") (pin "2") (pinfunction "D5_2") (pintype "bidirectional"))
      (node (ref "R12") (pin "1P") (pinfunction "1P_1P") (pintype "bidirectional"))
    )
    (net (code "111") (name "RGB_HSYNC") (class "Default")
      (node (ref "CON3") (pin "32") (pinfunction "HSYNC_32") (pintype "bidirectional"))
      (node (ref "IC8") (pin "27") (pinfunction "D24_27") (pintype "bidirectional"))
      (node (ref "R2") (pin "2P") (pinfunction "2P_2P") (pintype "bidirectional"))
    )
    (net (code "112") (name "RGB_ODCK") (class "Default")
      (node (ref "CON3") (pin "30") (pinfunction "CLK_30") (pintype "bidirectional"))
      (node (ref "R2") (pin "4P") (pinfunction "4P_4P") (pintype "bidirectional"))
    )
    (net (code "113") (name "RGB_PWM") (class "Default")
      (node (ref "JP4") (pin "3") (pinfunction "3_3") (pintype "passive"))
      (node (ref "JP6") (pin "1") (pinfunction "1_1") (pintype "passive"))
    )
    (net (code "114") (name "RGB_PWM_EN") (class "Default")
      (node (ref "JP4") (pin "2") (pinfunction "2_2") (pintype "passive"))
      (node (ref "T2") (pin "1") (pinfunction "G_1") (pintype "passive"))
    )
    (net (code "115") (name "RGB_VSYNC") (class "Default")
      (node (ref "CON3") (pin "33") (pinfunction "VSYNC_33") (pintype "bidirectional"))
      (node (ref "IC8") (pin "28") (pinfunction "D25_28") (pintype "bidirectional"))
      (node (ref "R2") (pin "1P") (pinfunction "1P_1P") (pintype "bidirectional"))
    )
    (net (code "116") (name "USB_D+") (class "Default")
      (node (ref "CON4") (pin "3") (pinfunction "D+_3") (pintype "bidirectional"))
      (node (ref "R23") (pin "1") (pinfunction "P$1_1") (pintype "passive"))
    )
    (net (code "117") (name "USB_D-") (class "Default")
      (node (ref "CON4") (pin "2") (pinfunction "D-_2") (pintype "bidirectional"))
      (node (ref "R22") (pin "1") (pinfunction "P$1_1") (pintype "passive"))
    )
    (net (code "118") (name "unconnected-(CON2-CEC-Pad13)") (class "Default")
      (node (ref "CON2") (pin "13") (pinfunction "CEC_13") (pintype "bidirectional"))
    )
    (net (code "119") (name "unconnected-(CON2-NC-Pad14)") (class "Default")
      (node (ref "CON2") (pin "14") (pinfunction "NC_14") (pintype "bidirectional"))
    )
    (net (code "120") (name "unconnected-(CON3-NC-Pad35)") (class "Default")
      (node (ref "CON3") (pin "35") (pinfunction "NC_35") (pintype "bidirectional"))
    )
    (net (code "121") (name "unconnected-(CON3-XL-Pad39)") (class "Default")
      (node (ref "CON3") (pin "39") (pinfunction "XL_39") (pintype "bidirectional"))
    )
    (net (code "122") (name "unconnected-(CON3-XR-Pad37)") (class "Default")
      (node (ref "CON3") (pin "37") (pinfunction "XR_37") (pintype "bidirectional"))
    )
    (net (code "123") (name "unconnected-(CON3-YD-Pad38)") (class "Default")
      (node (ref "CON3") (pin "38") (pinfunction "YD_38") (pintype "bidirectional"))
    )
    (net (code "124") (name "unconnected-(CON3-YU-Pad40)") (class "Default")
      (node (ref "CON3") (pin "40") (pinfunction "YU_40") (pintype "bidirectional"))
    )
    (net (code "125") (name "unconnected-(CON4-ID-Pad4)") (class "Default")
      (node (ref "CON4") (pin "4") (pinfunction "ID_4") (pintype "bidirectional"))
    )
    (net (code "126") (name "unconnected-(CON6-NC-Pad27)") (class "Default")
      (node (ref "CON6") (pin "27") (pinfunction "NC_27") (pintype "bidirectional"))
    )
    (net (code "127") (name "unconnected-(CON6-TP-Pad22)") (class "Default")
      (node (ref "CON6") (pin "22") (pinfunction "TP_22") (pintype "bidirectional"))
    )
    (net (code "128") (name "unconnected-(CON6-TP-Pad23)") (class "Default")
      (node (ref "CON6") (pin "23") (pinfunction "TP_23") (pintype "bidirectional"))
    )
    (net (code "129") (name "unconnected-(IC2-EN-Pad5)") (class "Default")
      (node (ref "IC2") (pin "5") (pinfunction "EN_5") (pintype "bidirectional"))
    )
    (net (code "130") (name "unconnected-(IC2-PG-Pad4)") (class "Default")
      (node (ref "IC2") (pin "4") (pinfunction "PG_4") (pintype "bidirectional"))
    )
    (net (code "131") (name "unconnected-(IC5-CTL1-Pad40)") (class "Default")
      (node (ref "IC5") (pin "40") (pinfunction "CTL1_40") (pintype "bidirectional"))
    )
    (net (code "132") (name "unconnected-(IC5-CTL2-Pad41)") (class "Default")
      (node (ref "IC5") (pin "41") (pinfunction "CTL2_41") (pintype "bidirectional"))
    )
    (net (code "133") (name "unconnected-(IC5-CTL3-Pad42)") (class "Default")
      (node (ref "IC5") (pin "42") (pinfunction "CTL3_42") (pintype "bidirectional"))
    )
    (net (code "134") (name "unconnected-(IC5-EXT_RES-Pad96)") (class "Default")
      (node (ref "IC5") (pin "96") (pinfunction "EXT_RES_96") (pintype "bidirectional"))
    )
    (net (code "135") (name "unconnected-(IC5-QO0-Pad49)") (class "Default")
      (node (ref "IC5") (pin "49") (pinfunction "QO0_49") (pintype "bidirectional"))
    )
    (net (code "136") (name "unconnected-(IC5-QO1-Pad50)") (class "Default")
      (node (ref "IC5") (pin "50") (pinfunction "QO1_50") (pintype "bidirectional"))
    )
    (net (code "137") (name "unconnected-(IC5-QO2-Pad51)") (class "Default")
      (node (ref "IC5") (pin "51") (pinfunction "QO2_51") (pintype "bidirectional"))
    )
    (net (code "138") (name "unconnected-(IC5-QO3-Pad52)") (class "Default")
      (node (ref "IC5") (pin "52") (pinfunction "QO3_52") (pintype "bidirectional"))
    )
    (net (code "139") (name "unconnected-(IC5-QO4-Pad53)") (class "Default")
      (node (ref "IC5") (pin "53") (pinfunction "QO4_53") (pintype "bidirectional"))
    )
    (net (code "140") (name "unconnected-(IC5-QO5-Pad54)") (class "Default")
      (node (ref "IC5") (pin "54") (pinfunction "QO5_54") (pintype "bidirectional"))
    )
    (net (code "141") (name "unconnected-(IC5-QO6-Pad55)") (class "Default")
      (node (ref "IC5") (pin "55") (pinfunction "QO6_55") (pintype "bidirectional"))
    )
    (net (code "142") (name "unconnected-(IC5-QO7-Pad56)") (class "Default")
      (node (ref "IC5") (pin "56") (pinfunction "QO7_56") (pintype "bidirectional"))
    )
    (net (code "143") (name "unconnected-(IC5-QO8-Pad59)") (class "Default")
      (node (ref "IC5") (pin "59") (pinfunction "QO8_59") (pintype "bidirectional"))
    )
    (net (code "144") (name "unconnected-(IC5-QO9-Pad60)") (class "Default")
      (node (ref "IC5") (pin "60") (pinfunction "QO9_60") (pintype "bidirectional"))
    )
    (net (code "145") (name "unconnected-(IC5-QO10-Pad61)") (class "Default")
      (node (ref "IC5") (pin "61") (pinfunction "QO10_61") (pintype "bidirectional"))
    )
    (net (code "146") (name "unconnected-(IC5-QO11-Pad62)") (class "Default")
      (node (ref "IC5") (pin "62") (pinfunction "QO11_62") (pintype "bidirectional"))
    )
    (net (code "147") (name "unconnected-(IC5-QO12-Pad63)") (class "Default")
      (node (ref "IC5") (pin "63") (pinfunction "QO12_63") (pintype "bidirectional"))
    )
    (net (code "148") (name "unconnected-(IC5-QO13-Pad64)") (class "Default")
      (node (ref "IC5") (pin "64") (pinfunction "QO13_64") (pintype "bidirectional"))
    )
    (net (code "149") (name "unconnected-(IC5-QO14-Pad65)") (class "Default")
      (node (ref "IC5") (pin "65") (pinfunction "QO14_65") (pintype "bidirectional"))
    )
    (net (code "150") (name "unconnected-(IC5-QO15-Pad66)") (class "Default")
      (node (ref "IC5") (pin "66") (pinfunction "QO15_66") (pintype "bidirectional"))
    )
    (net (code "151") (name "unconnected-(IC5-QO16-Pad69)") (class "Default")
      (node (ref "IC5") (pin "69") (pinfunction "QO16_69") (pintype "bidirectional"))
    )
    (net (code "152") (name "unconnected-(IC5-QO17-Pad70)") (class "Default")
      (node (ref "IC5") (pin "70") (pinfunction "QO17_70") (pintype "bidirectional"))
    )
    (net (code "153") (name "unconnected-(IC5-QO18-Pad71)") (class "Default")
      (node (ref "IC5") (pin "71") (pinfunction "QO18_71") (pintype "bidirectional"))
    )
    (net (code "154") (name "unconnected-(IC5-QO19-Pad72)") (class "Default")
      (node (ref "IC5") (pin "72") (pinfunction "QO19_72") (pintype "bidirectional"))
    )
    (net (code "155") (name "unconnected-(IC5-QO20-Pad73)") (class "Default")
      (node (ref "IC5") (pin "73") (pinfunction "QO20_73") (pintype "bidirectional"))
    )
    (net (code "156") (name "unconnected-(IC5-QO21-Pad74)") (class "Default")
      (node (ref "IC5") (pin "74") (pinfunction "QO21_74") (pintype "bidirectional"))
    )
    (net (code "157") (name "unconnected-(IC5-QO22-Pad75)") (class "Default")
      (node (ref "IC5") (pin "75") (pinfunction "QO22_75") (pintype "bidirectional"))
    )
    (net (code "158") (name "unconnected-(IC5-QO23-Pad77)") (class "Default")
      (node (ref "IC5") (pin "77") (pinfunction "QO23_77") (pintype "bidirectional"))
    )
    (net (code "159") (name "unconnected-(IC5-SCDT-Pad8)") (class "Default")
      (node (ref "IC5") (pin "8") (pinfunction "SCDT_8") (pintype "bidirectional"))
    )
    (net (code "160") (name "unconnected-(IC5-~{PDO}-Pad9)") (class "Default")
      (node (ref "IC5") (pin "9") (pinfunction "~{PDO}_9") (pintype "bidirectional"))
    )
    (net (code "161") (name "unconnected-(IC5-~{PD}-Pad2)") (class "Default")
      (node (ref "IC5") (pin "2") (pinfunction "~{PD}_2") (pintype "bidirectional"))
    )
    (net (code "162") (name "unconnected-(IC6-(PCINT18{slash}INT0)PD2-Pad32)") (class "Default")
      (node (ref "IC6") (pin "32") (pinfunction "(PCINT18/INT0)PD2_32") (pintype "bidirectional"))
    )
    (net (code "163") (name "unconnected-(IC6-(PCINT19{slash}OC2B{slash}INT1)PD3-Pad1)") (class "Default")
      (node (ref "IC6") (pin "1") (pinfunction "(PCINT19/OC2B/INT1)PD3_1") (pintype "bidirectional"))
    )
    (net (code "164") (name "unconnected-(IC6-(PCINT20{slash}XCK{slash}T0)PD4-Pad2)") (class "Default")
      (node (ref "IC6") (pin "2") (pinfunction "(PCINT20/XCK/T0)PD4_2") (pintype "bidirectional"))
    )
    (net (code "165") (name "unconnected-(IC6-(PCINT21{slash}OC0B{slash}T1)PD5-Pad9)") (class "Default")
      (node (ref "IC6") (pin "9") (pinfunction "(PCINT21/OC0B/T1)PD5_9") (pintype "bidirectional"))
    )
    (net (code "166") (name "unconnected-(IC6-(PCINT22{slash}OC0A{slash}AIN0)PD6-Pad10)") (class "Default")
      (node (ref "IC6") (pin "10") (pinfunction "(PCINT22/OC0A/AIN0)PD6_10") (pintype "bidirectional"))
    )
    (net (code "167") (name "unconnected-(IC6-(PCINT23{slash}AIN1)PD7-Pad11)") (class "Default")
      (node (ref "IC6") (pin "11") (pinfunction "(PCINT23/AIN1)PD7_11") (pintype "bidirectional"))
    )
    (net (code "168") (name "unconnected-(IC6-ADC6-Pad19)") (class "Default")
      (node (ref "IC6") (pin "19") (pinfunction "ADC6_19") (pintype "bidirectional"))
    )
    (net (code "169") (name "unconnected-(IC6-ADC7-Pad22)") (class "Default")
      (node (ref "IC6") (pin "22") (pinfunction "ADC7_22") (pintype "bidirectional"))
    )
    (net (code "170") (name "unconnected-(IC6-PB0(PCINT0{slash}CLKO{slash}ICP1)-Pad12)") (class "Default")
      (node (ref "IC6") (pin "12") (pinfunction "PB0(PCINT0/CLKO/ICP1)_12") (pintype "bidirectional"))
    )
    (net (code "171") (name "unconnected-(IC6-PB2(SS{slash}OC1B{slash}PCINT2)-Pad14)") (class "Default")
      (node (ref "IC6") (pin "14") (pinfunction "PB2(SS/OC1B/PCINT2)_14") (pintype "bidirectional"))
    )
    (net (code "172") (name "unconnected-(IC6-PC1(ADC1{slash}PCINT9)-Pad24)") (class "Default")
      (node (ref "IC6") (pin "24") (pinfunction "PC1(ADC1/PCINT9)_24") (pintype "bidirectional"))
    )
    (net (code "173") (name "unconnected-(IC6-PC2(ADC2{slash}PCINT10)-Pad25)") (class "Default")
      (node (ref "IC6") (pin "25") (pinfunction "PC2(ADC2/PCINT10)_25") (pintype "bidirectional"))
    )
    (net (code "174") (name "unconnected-(IC6-PC3(ADC3{slash}PCINT11)-Pad26)") (class "Default")
      (node (ref "IC6") (pin "26") (pinfunction "PC3(ADC3/PCINT11)_26") (pintype "bidirectional"))
    )
    (net (code "175") (name "unconnected-(IC7-CBUS0-Pad23)") (class "Default")
      (node (ref "IC7") (pin "23") (pinfunction "CBUS0_23") (pintype "bidirectional"))
    )
    (net (code "176") (name "unconnected-(IC7-CBUS1-Pad22)") (class "Default")
      (node (ref "IC7") (pin "22") (pinfunction "CBUS1_22") (pintype "bidirectional"))
    )
    (net (code "177") (name "unconnected-(IC7-CBUS2-Pad13)") (class "Default")
      (node (ref "IC7") (pin "13") (pinfunction "CBUS2_13") (pintype "bidirectional"))
    )
    (net (code "178") (name "unconnected-(IC7-CBUS3-Pad14)") (class "Default")
      (node (ref "IC7") (pin "14") (pinfunction "CBUS3_14") (pintype "bidirectional"))
    )
    (net (code "179") (name "unconnected-(IC7-CBUS4-Pad12)") (class "Default")
      (node (ref "IC7") (pin "12") (pinfunction "CBUS4_12") (pintype "bidirectional"))
    )
    (net (code "180") (name "unconnected-(IC7-OSCI-Pad27)") (class "Default")
      (node (ref "IC7") (pin "27") (pinfunction "OSCI_27") (pintype "input"))
    )
    (net (code "181") (name "unconnected-(IC7-OSCO-Pad28)") (class "Default")
      (node (ref "IC7") (pin "28") (pinfunction "OSCO_28") (pintype "output"))
    )
    (net (code "182") (name "unconnected-(IC7-~{CTS}-Pad11)") (class "Default")
      (node (ref "IC7") (pin "11") (pinfunction "~{CTS}_11") (pintype "input"))
    )
    (net (code "183") (name "unconnected-(IC7-~{DCD}-Pad10)") (class "Default")
      (node (ref "IC7") (pin "10") (pinfunction "~{DCD}_10") (pintype "input"))
    )
    (net (code "184") (name "unconnected-(IC7-~{DSR}-Pad9)") (class "Default")
      (node (ref "IC7") (pin "9") (pinfunction "~{DSR}_9") (pintype "input"))
    )
    (net (code "185") (name "unconnected-(IC7-~{DTR}-Pad2)") (class "Default")
      (node (ref "IC7") (pin "2") (pinfunction "~{DTR}_2") (pintype "output"))
    )
    (net (code "186") (name "unconnected-(IC7-~{RI}-Pad6)") (class "Default")
      (node (ref "IC7") (pin "6") (pinfunction "~{RI}_6") (pintype "input"))
    )
    (net (code "187") (name "unconnected-(IC7-~{RTS}-Pad3)") (class "Default")
      (node (ref "IC7") (pin "3") (pinfunction "~{RTS}_3") (pintype "output"))
    )
    (net (code "188") (name "unconnected-(IC8-CLKIN-Pad31)") (class "Default")
      (node (ref "IC8") (pin "31") (pinfunction "CLKIN_31") (pintype "bidirectional"))
    )
    (net (code "189") (name "unconnected-(IC8-CLKSEL-Pad17)") (class "Default")
      (node (ref "IC8") (pin "17") (pinfunction "CLKSEL_17") (pintype "bidirectional"))
    )
    (net (code "190") (name "unconnected-(IC8-~{SHTDN}-Pad32)") (class "Default")
      (node (ref "IC8") (pin "32") (pinfunction "~{SHTDN}_32") (pintype "bidirectional"))
    )
  )
)
